# EEZ_PSU_power_board_r5B9.net
KiCad netlist of a schematic drawn in EAGLE
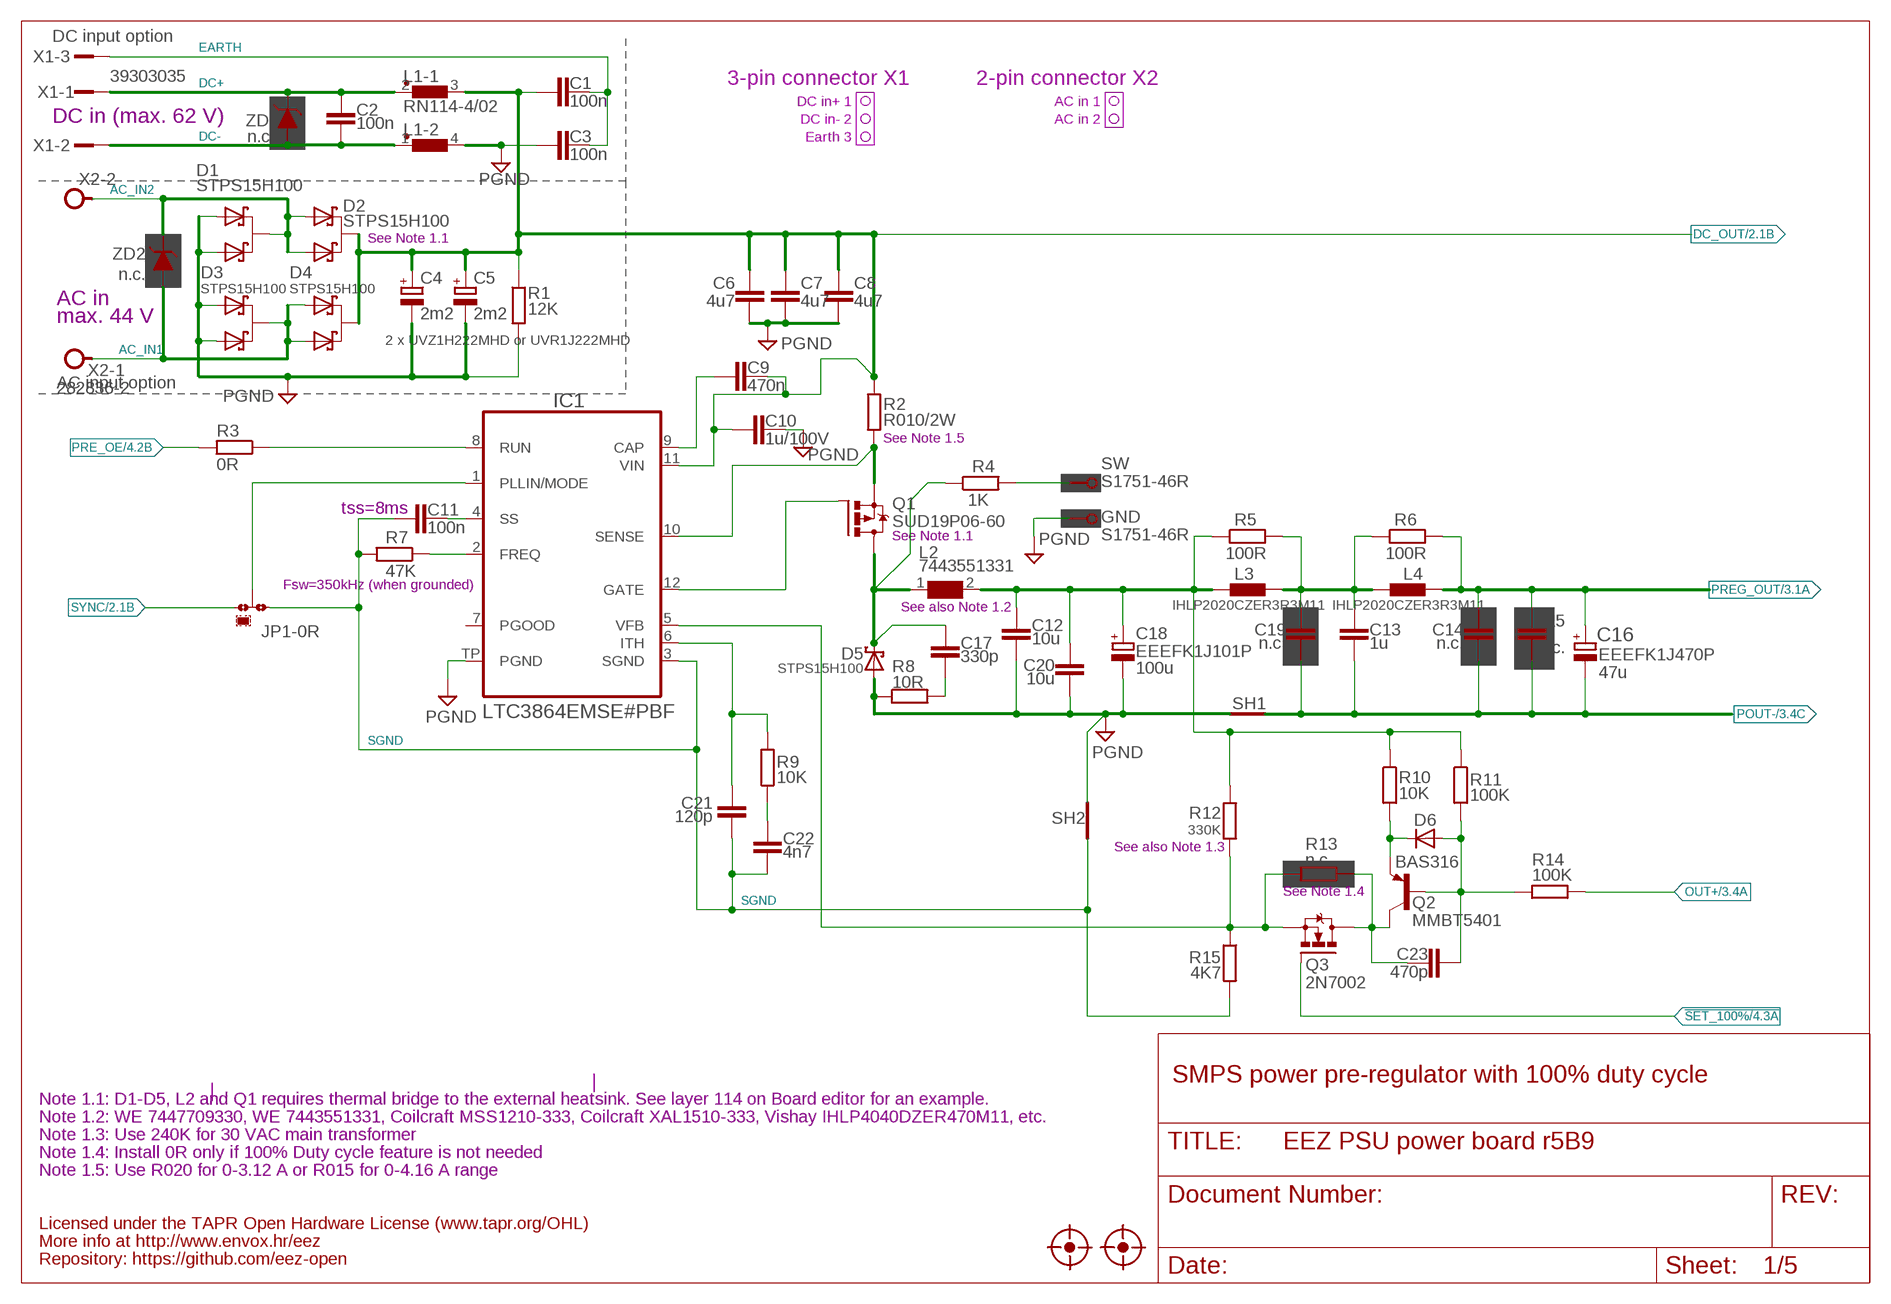
[diagram p0: schematic, sheet 1]
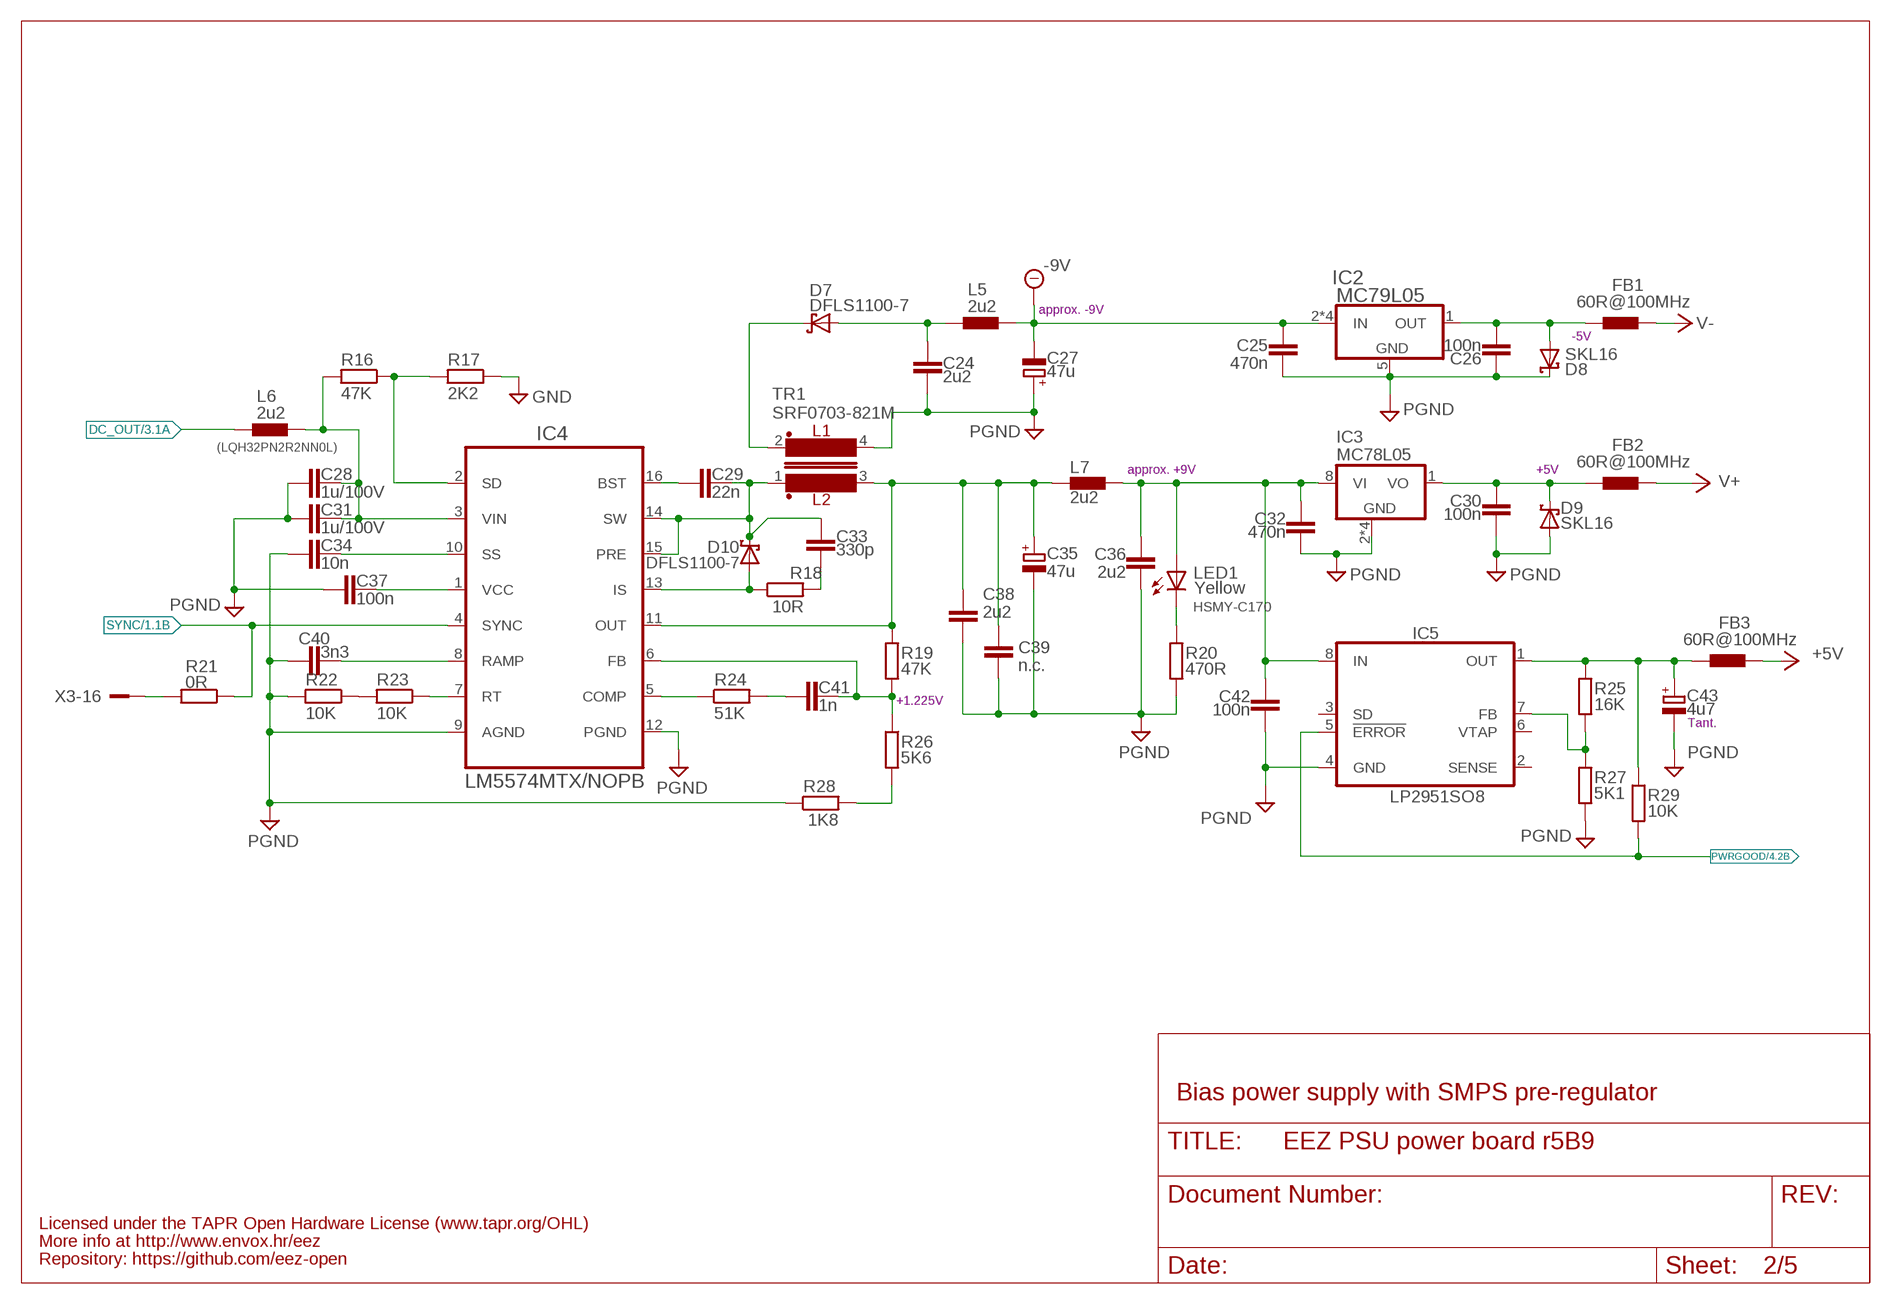
[diagram p1: schematic, sheet 2]
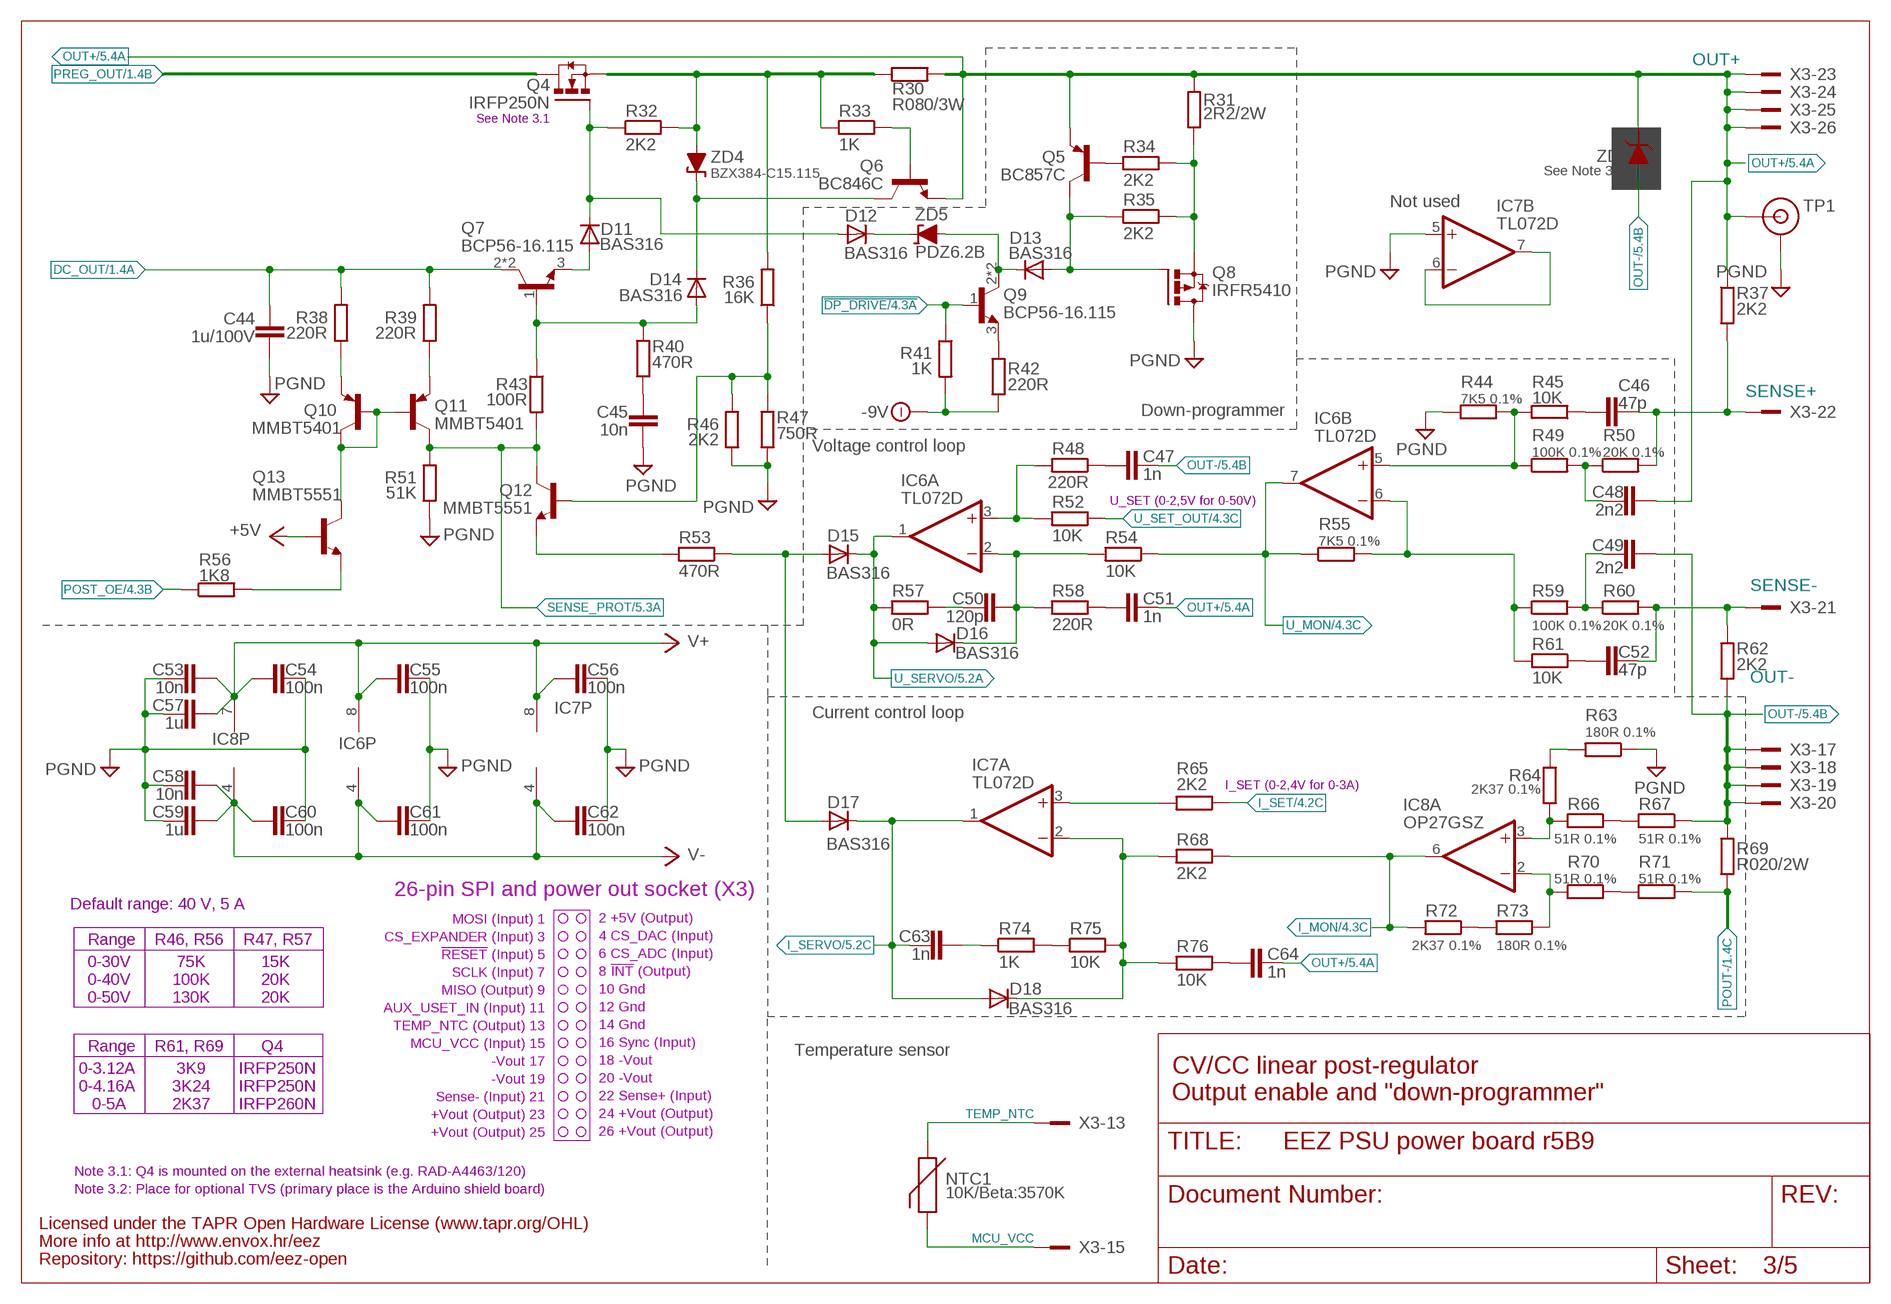
[diagram p2: schematic, sheet 3]
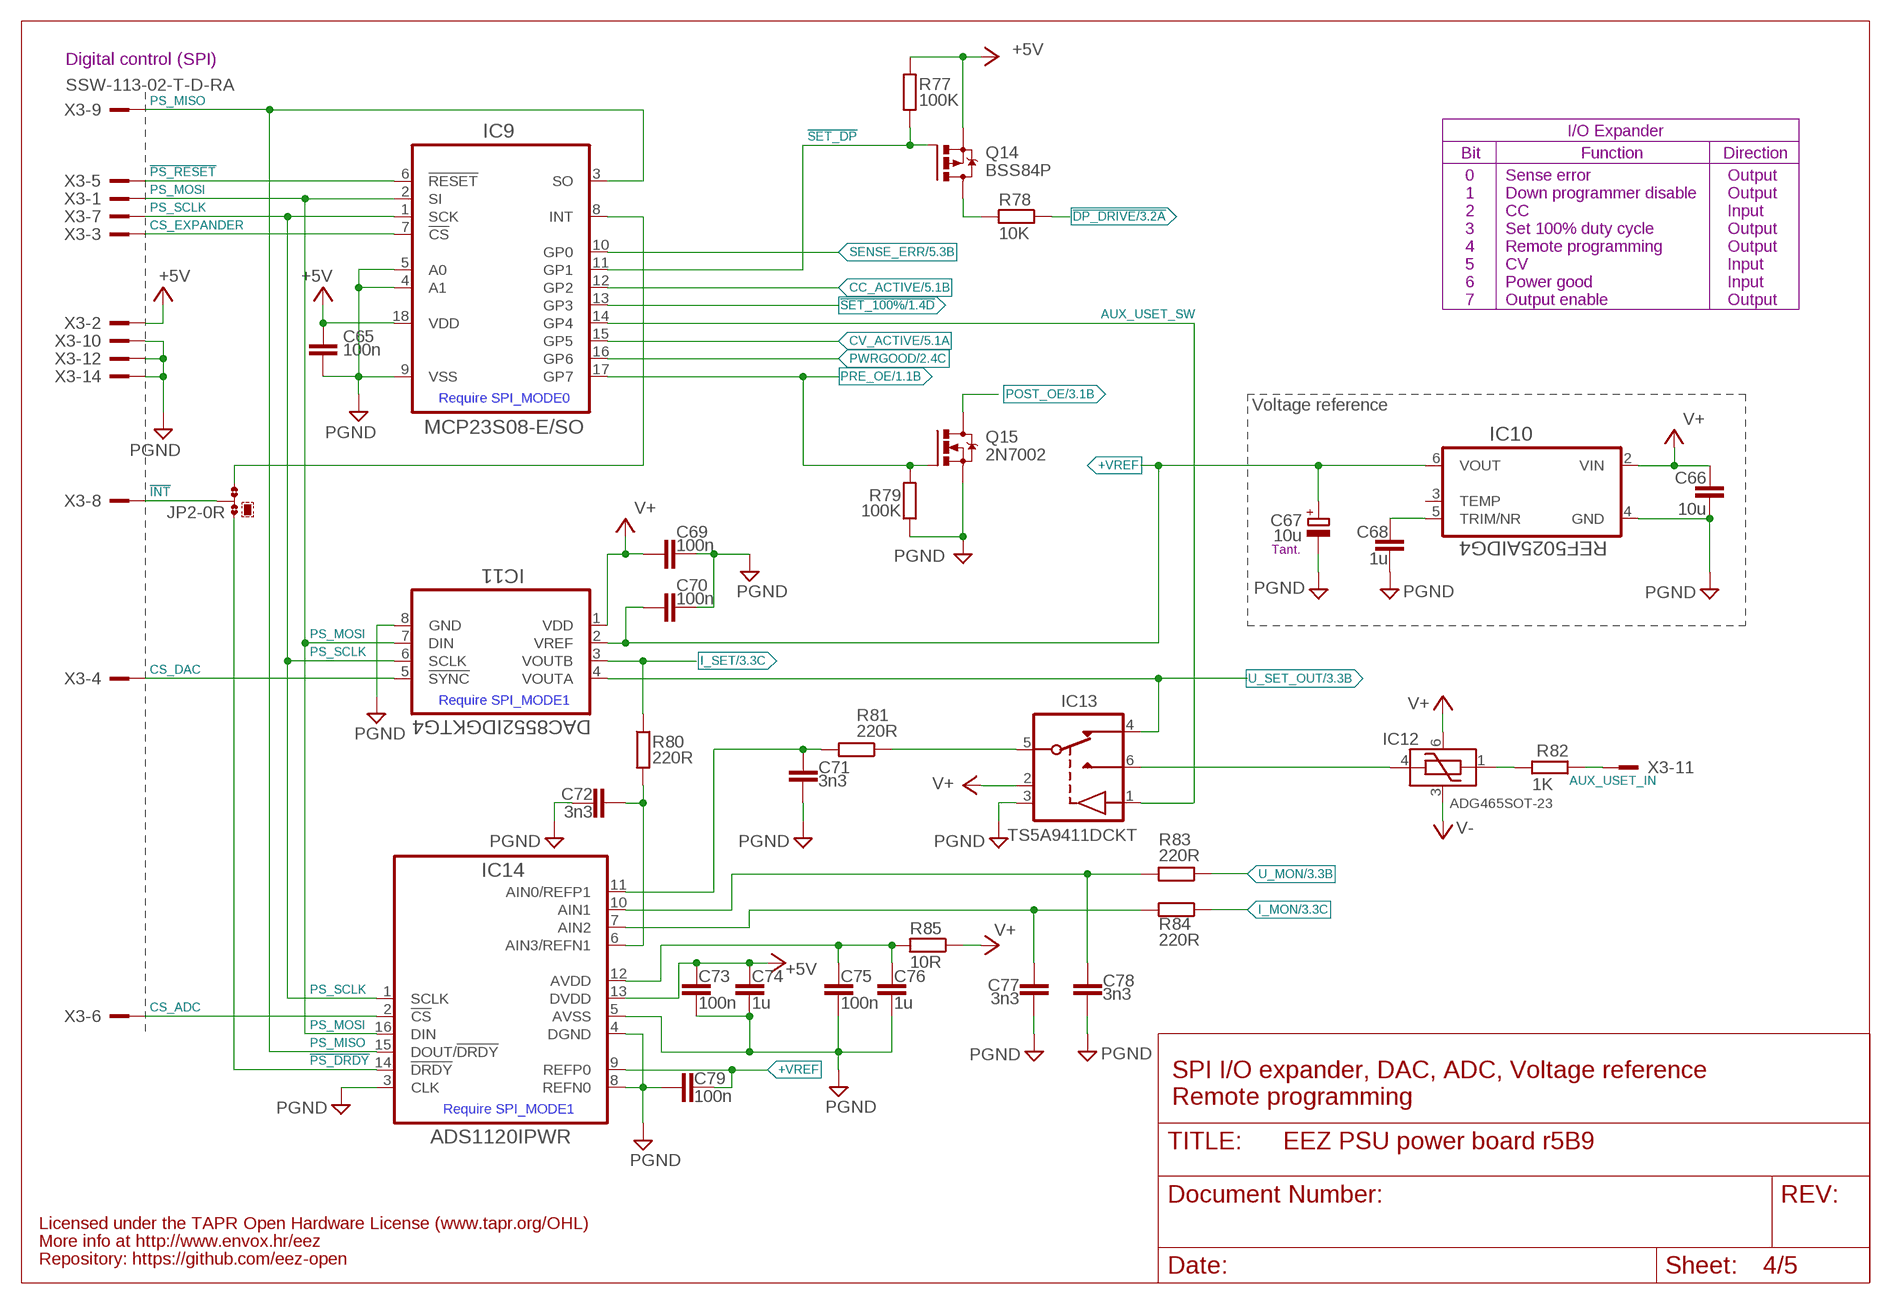
[diagram p3: schematic, sheet 4]
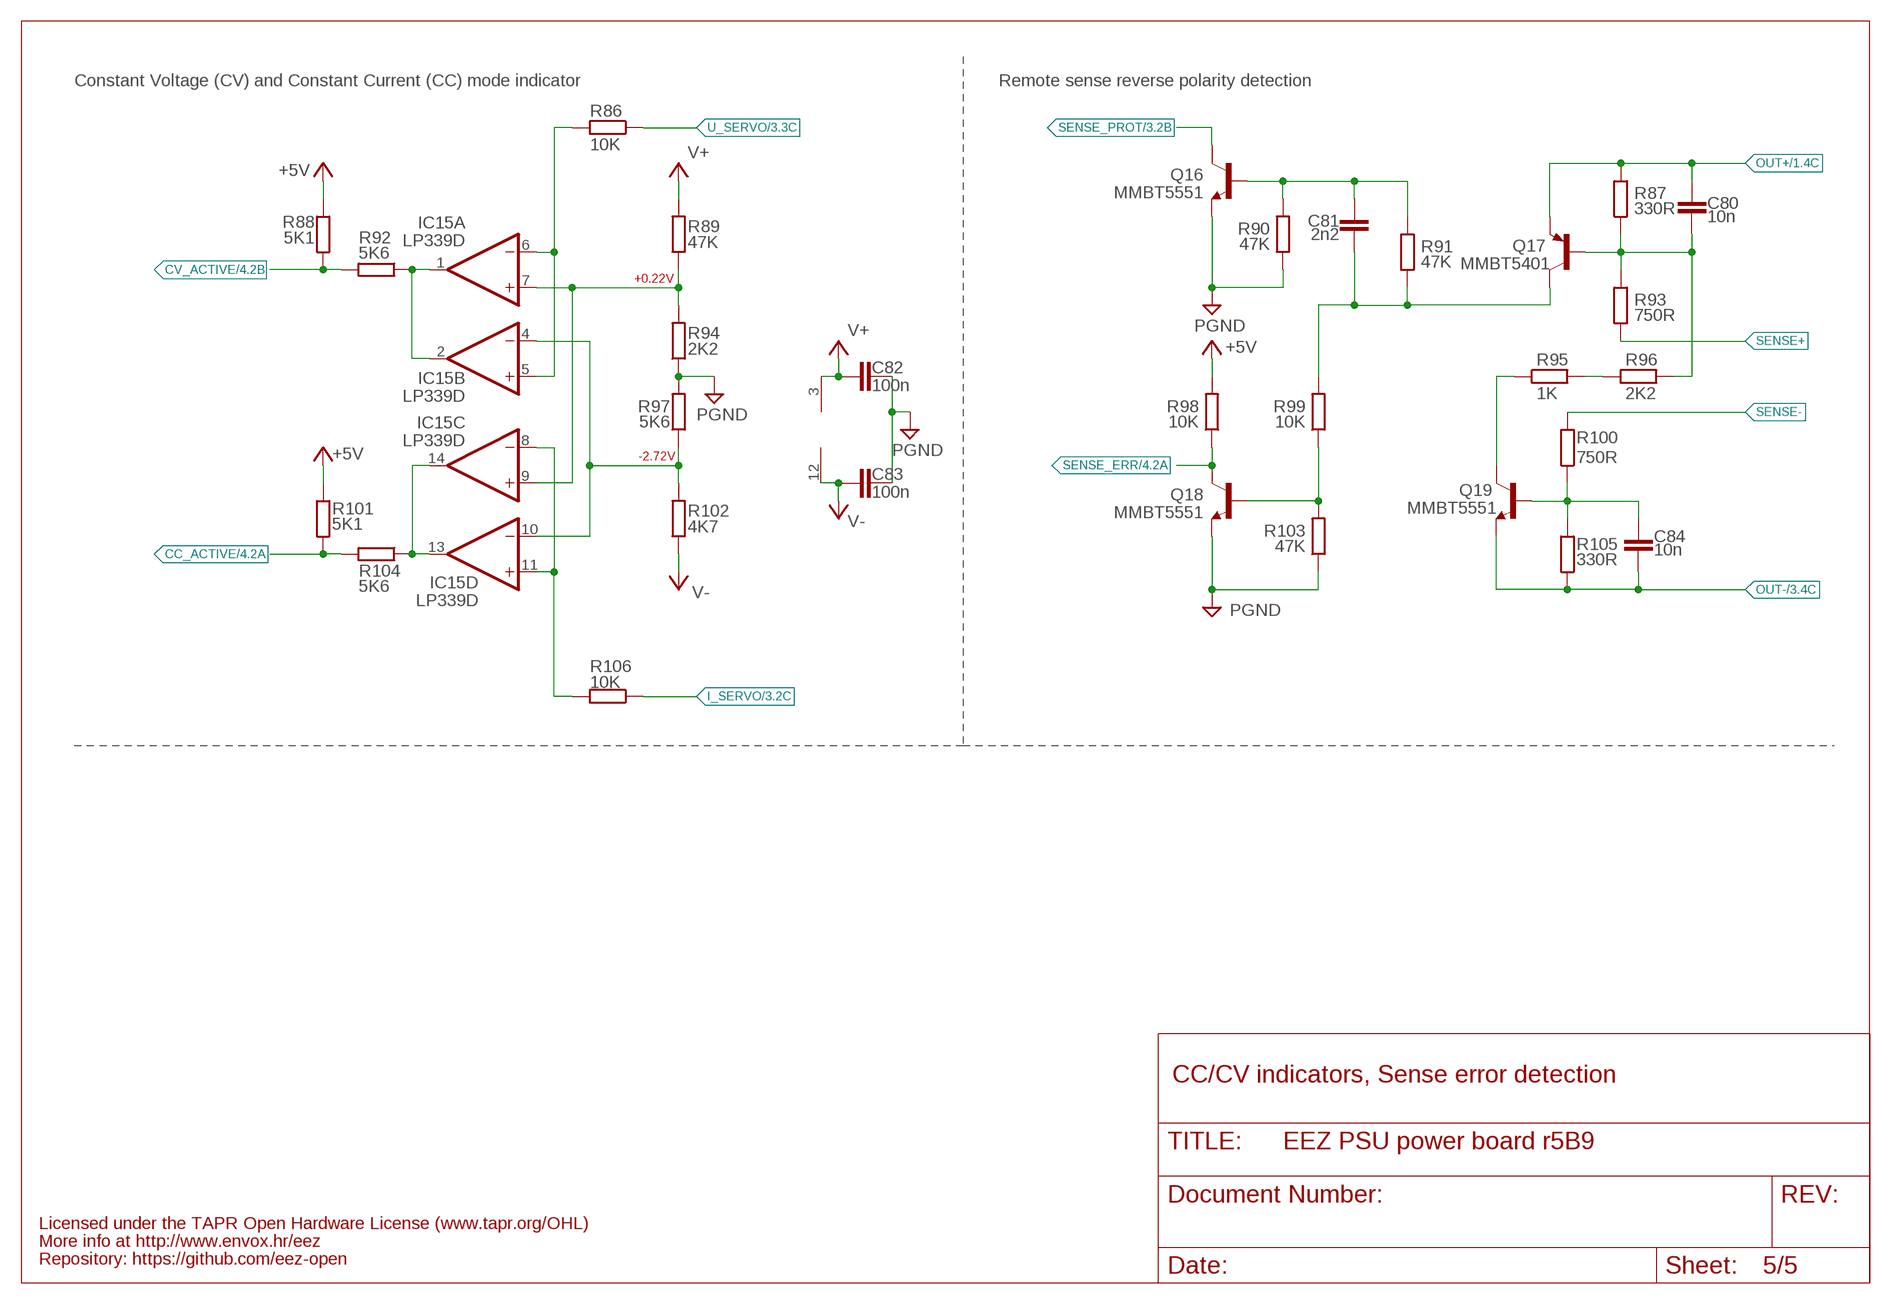
[diagram p4: schematic, sheet 5]

(export (version "E")
  (design (tool "Eeschema 10.0.6"))
  (components
    (comp (ref "C65")
      (value "100n")
      (footprint "eagle-import:C0603")
      (libsource (lib "eagle-import") (part "C-EUC0603"))
    )
    (comp (ref "C66")
      (value "10u")
      (footprint "eagle-import:C1210")
      (libsource (lib "eagle-import") (part "C-EUC1210"))
    )
    (comp (ref "C67")
      (value "10u")
      (footprint "eagle-import:EC1206")
      (libsource (lib "eagle-import") (part "ECAP1206"))
    )
    (comp (ref "C68")
      (value "1u")
      (footprint "eagle-import:C0805")
      (libsource (lib "eagle-import") (part "C-EUC0805"))
    )
    (comp (ref "C69")
      (value "100n")
      (footprint "eagle-import:C0603")
      (libsource (lib "eagle-import") (part "C-EUC0603"))
    )
    (comp (ref "C70")
      (value "100n")
      (footprint "eagle-import:C0603")
      (libsource (lib "eagle-import") (part "C-EUC0603"))
    )
    (comp (ref "C71")
      (value "3n3")
      (footprint "eagle-import:C0805")
      (libsource (lib "eagle-import") (part "C-EUC0805"))
    )
    (comp (ref "C72")
      (value "3n3")
      (footprint "eagle-import:C0805")
      (libsource (lib "eagle-import") (part "C-EUC0805"))
    )
    (comp (ref "C73")
      (value "100n")
      (footprint "eagle-import:C0603")
      (libsource (lib "eagle-import") (part "C-EUC0603"))
    )
    (comp (ref "C74")
      (value "1u")
      (footprint "eagle-import:C0805")
      (libsource (lib "eagle-import") (part "C-EUC0805"))
    )
    (comp (ref "C75")
      (value "100n")
      (footprint "eagle-import:C0603")
      (libsource (lib "eagle-import") (part "C-EUC0603"))
    )
    (comp (ref "C76")
      (value "1u")
      (footprint "eagle-import:C0805")
      (libsource (lib "eagle-import") (part "C-EUC0805"))
    )
    (comp (ref "C77")
      (value "3n3")
      (footprint "eagle-import:C0805")
      (libsource (lib "eagle-import") (part "C-EUC0805"))
    )
    (comp (ref "C78")
      (value "3n3")
      (footprint "eagle-import:C0805")
      (libsource (lib "eagle-import") (part "C-EUC0805"))
    )
    (comp (ref "C79")
      (value "100n")
      (footprint "eagle-import:C0603")
      (libsource (lib "eagle-import") (part "C-EUC0603"))
    )
    (comp (ref "IC9")
      (value "MCP23S08-E/SO")
      (footprint "eagle-import:SOIC127P1030X265-18N")
      (libsource (lib "eagle-import") (part "MCP23S08"))
    )
    (comp (ref "IC10")
      (value "REF5025AIDG4")
      (footprint "eagle-import:SOIC127P600X175-8N")
      (libsource (lib "eagle-import") (part "REF50XX"))
    )
    (comp (ref "IC11")
      (value "DAC8552IDGKTG4")
      (footprint "eagle-import:DGK8-M")
      (libsource (lib "eagle-import") (part "DAC8552_DGK_8M"))
    )
    (comp (ref "IC12")
      (value "ADG465SOT-23")
      (footprint "eagle-import:SOT95P280X145-6N")
      (libsource (lib "eagle-import") (part "ADG465SOT-23"))
    )
    (comp (ref "IC13")
      (value "TS5A9411DCKT")
      (footprint "eagle-import:SOT65P210X110-6N")
      (libsource (lib "eagle-import") (part "TS5A9411DCKT"))
    )
    (comp (ref "IC14")
      (value "ADS1120IPWR")
      (footprint "eagle-import:PW(R-PDSO-G16)")
      (libsource (lib "eagle-import") (part "ADS1120TSSOP-16"))
    )
    (comp (ref "JP2")
      (value "0R-JUMPA")
      (footprint "eagle-import:A0R-JMP")
      (libsource (lib "eagle-import") (part "0R-JUMPA"))
    )
    (comp (ref "Q14")
      (value "BSS84P")
      (footprint "eagle-import:SOT95P237X112-3N")
      (fields (field (name "MPN") "IRLML2246TRPBF"))
      (libsource (lib "eagle-import") (part "IRLML2246TRPBF"))
    )
    (comp (ref "Q15")
      (value "2N7002")
      (footprint "eagle-import:SOT103P240X110-3N")
      (fields
        (field (name "MPN") "2N7002-7-F")
        (field (name "MPN_1") "2N7002-7-F")
        (field (name "OC_FARNELL") "1713823")
        (field (name "OC_NEWARK") "25R5679")
        (field (name "PACKAGE") "SOT-23-3")
        (field (name "SUPPLIER") "DIODES INC.")
      )
      (libsource (lib "eagle-import") (part "2N7002"))
    )
    (comp (ref "R77")
      (value "100K")
      (footprint "eagle-import:R0805")
      (libsource (lib "eagle-import") (part "R-EU_R0805"))
    )
    (comp (ref "R78")
      (value "10K")
      (footprint "eagle-import:R0805")
      (libsource (lib "eagle-import") (part "R-EU_R0805"))
    )
    (comp (ref "R79")
      (value "100K")
      (footprint "eagle-import:R0805")
      (libsource (lib "eagle-import") (part "R-EU_R0805"))
    )
    (comp (ref "R80")
      (value "220R")
      (footprint "eagle-import:R0805")
      (libsource (lib "eagle-import") (part "R-EU_R0805"))
    )
    (comp (ref "R81")
      (value "220R")
      (footprint "eagle-import:R0805")
      (libsource (lib "eagle-import") (part "R-EU_R0805"))
    )
    (comp (ref "R82")
      (value "1K")
      (footprint "eagle-import:R0805")
      (libsource (lib "eagle-import") (part "R-EU_R0805"))
    )
    (comp (ref "R83")
      (value "220R")
      (footprint "eagle-import:R0805")
      (libsource (lib "eagle-import") (part "R-EU_R0805"))
    )
    (comp (ref "R84")
      (value "220R")
      (footprint "eagle-import:R0805")
      (libsource (lib "eagle-import") (part "R-EU_R0805"))
    )
    (comp (ref "R85")
      (value "10R")
      (footprint "eagle-import:R1206")
      (libsource (lib "eagle-import") (part "R-EU_R1206"))
    )
    (comp (ref "X3")
      (value "SSW-113-02-T-D-RA")
      (footprint "eagle-import:SSW-113-02-T-D-RA")
      (fields (field (name "FARNELL") "1805583"))
      (libsource (lib "eagle-import") (part "SSW-113-02-T-D-RA"))
    )
    (comp (ref "C24")
      (value "2u2")
      (footprint "eagle-import:C0805")
      (libsource (lib "eagle-import") (part "C-EUC0805"))
    )
    (comp (ref "C25")
      (value "470n")
      (footprint "eagle-import:C0805")
      (libsource (lib "eagle-import") (part "C-EUC0805"))
    )
    (comp (ref "C26")
      (value "100n")
      (footprint "eagle-import:C0603")
      (libsource (lib "eagle-import") (part "C-EUC0603"))
    )
    (comp (ref "C27")
      (value "47u")
      (footprint "eagle-import:CAPAE660X610N")
      (libsource (lib "eagle-import") (part "ECAPPANASONIC_H"))
    )
    (comp (ref "C28")
      (value "1u/100V")
      (footprint "eagle-import:C1206")
      (libsource (lib "eagle-import") (part "C-EUC1206"))
    )
    (comp (ref "C29")
      (value "22n")
      (footprint "eagle-import:C0805")
      (libsource (lib "eagle-import") (part "C-EUC0805"))
    )
    (comp (ref "C30")
      (value "100n")
      (footprint "eagle-import:C0603")
      (libsource (lib "eagle-import") (part "C-EUC0603"))
    )
    (comp (ref "C31")
      (value "1u/100V")
      (footprint "eagle-import:C1206")
      (libsource (lib "eagle-import") (part "C-EUC1206"))
    )
    (comp (ref "C32")
      (value "470n")
      (footprint "eagle-import:C0805")
      (libsource (lib "eagle-import") (part "C-EUC0805"))
    )
    (comp (ref "C33")
      (value "330p")
      (footprint "eagle-import:C0805")
      (libsource (lib "eagle-import") (part "C-EUC0805"))
    )
    (comp (ref "C34")
      (value "10n")
      (footprint "eagle-import:C0805")
      (libsource (lib "eagle-import") (part "C-EUC0805"))
    )
    (comp (ref "C35")
      (value "47u")
      (footprint "eagle-import:CAPAE660X610N")
      (libsource (lib "eagle-import") (part "ECAPPANASONIC_H"))
    )
    (comp (ref "C36")
      (value "2u2")
      (footprint "eagle-import:C0805")
      (libsource (lib "eagle-import") (part "C-EUC0805"))
    )
    (comp (ref "C37")
      (value "100n")
      (footprint "eagle-import:C0603")
      (libsource (lib "eagle-import") (part "C-EUC0603"))
    )
    (comp (ref "C38")
      (value "2u2")
      (footprint "eagle-import:C0805")
      (libsource (lib "eagle-import") (part "C-EUC0805"))
    )
    (comp (ref "C39")
      (value "n.c.")
      (footprint "eagle-import:C0805")
      (libsource (lib "eagle-import") (part "C-EUC0805"))
    )
    (comp (ref "C40")
      (value "3n3")
      (footprint "eagle-import:C0805")
      (libsource (lib "eagle-import") (part "C-EUC0805"))
    )
    (comp (ref "C41")
      (value "1n")
      (footprint "eagle-import:C0805")
      (libsource (lib "eagle-import") (part "C-EUC0805"))
    )
    (comp (ref "C42")
      (value "100n")
      (footprint "eagle-import:C0603")
      (libsource (lib "eagle-import") (part "C-EUC0603"))
    )
    (comp (ref "C43")
      (value "4u7")
      (footprint "eagle-import:EC1206")
      (libsource (lib "eagle-import") (part "ECAP1206"))
    )
    (comp (ref "D7")
      (value "DFLS1100-7")
      (footprint "eagle-import:SOD123")
      (libsource (lib "eagle-import") (part "SCHOTTKYSOD123"))
    )
    (comp (ref "D8")
      (value "SKL16")
      (footprint "eagle-import:SOD123")
      (libsource (lib "eagle-import") (part "SCHOTTKYSOD123"))
    )
    (comp (ref "D9")
      (value "SKL16")
      (footprint "eagle-import:SOD123")
      (libsource (lib "eagle-import") (part "SCHOTTKYSOD123"))
    )
    (comp (ref "D10")
      (value "DFLS1100-7")
      (footprint "eagle-import:SOD123")
      (libsource (lib "eagle-import") (part "SCHOTTKYSOD123"))
    )
    (comp (ref "FB1")
      (value "60R@100MHz")
      (footprint "eagle-import:BEAD0603")
      (libsource (lib "eagle-import") (part "FERRITE_BEAD0603"))
    )
    (comp (ref "FB2")
      (value "60R@100MHz")
      (footprint "eagle-import:BEAD0603")
      (libsource (lib "eagle-import") (part "FERRITE_BEAD0603"))
    )
    (comp (ref "FB3")
      (value "60R@100MHz")
      (footprint "eagle-import:BEAD0603")
      (libsource (lib "eagle-import") (part "FERRITE_BEAD0603"))
    )
    (comp (ref "IC2")
      (value "MC79L05")
      (footprint "eagle-import:SOIC127P600X173-8N")
      (libsource (lib "eagle-import") (part "MC79LXXSOIC"))
    )
    (comp (ref "IC3")
      (value "MC78L05")
      (footprint "eagle-import:SOIC127P600X173-8N")
      (libsource (lib "eagle-import") (part "MC78LXXSOIC8"))
    )
    (comp (ref "IC4")
      (value "LM5574MTX/NOPB")
      (footprint "eagle-import:SOP65P640X110-16N")
      (fields (field (name "MPN") "LM5574MT"))
      (libsource (lib "eagle-import") (part "LM5574"))
    )
    (comp (ref "IC5")
      (value "LP2951SO8")
      (footprint "eagle-import:SOIC127P600X175-8N")
      (libsource (lib "eagle-import") (part "LP2951SO8"))
    )
    (comp (ref "L5")
      (value "2u2")
      (footprint "eagle-import:L1210")
      (libsource (lib "eagle-import") (part "L1210"))
    )
    (comp (ref "L6")
      (value "2u2")
      (footprint "eagle-import:L1210")
      (libsource (lib "eagle-import") (part "L1210"))
    )
    (comp (ref "L7")
      (value "2u2")
      (footprint "eagle-import:L1210")
      (libsource (lib "eagle-import") (part "L1210"))
    )
    (comp (ref "LED1")
      (value "HSMY-C170")
      (footprint "eagle-import:LED_0805")
      (libsource (lib "eagle-import") (part "LED0805"))
    )
    (comp (ref "R16")
      (value "47K")
      (footprint "eagle-import:R0805")
      (libsource (lib "eagle-import") (part "R-EU_R0805"))
    )
    (comp (ref "R17")
      (value "2K2")
      (footprint "eagle-import:R0805")
      (libsource (lib "eagle-import") (part "R-EU_R0805"))
    )
    (comp (ref "R18")
      (value "10R")
      (footprint "eagle-import:R1206")
      (libsource (lib "eagle-import") (part "R-EU_R1206"))
    )
    (comp (ref "R19")
      (value "47K")
      (footprint "eagle-import:R0805")
      (libsource (lib "eagle-import") (part "R-EU_R0805"))
    )
    (comp (ref "R20")
      (value "470R")
      (footprint "eagle-import:R0805")
      (libsource (lib "eagle-import") (part "R-EU_R0805"))
    )
    (comp (ref "R21")
      (value "0R")
      (footprint "eagle-import:R0805")
      (libsource (lib "eagle-import") (part "R-EU_R0805"))
    )
    (comp (ref "R22")
      (value "10K")
      (footprint "eagle-import:R0805")
      (libsource (lib "eagle-import") (part "R-EU_R0805"))
    )
    (comp (ref "R23")
      (value "10K")
      (footprint "eagle-import:R0805")
      (libsource (lib "eagle-import") (part "R-EU_R0805"))
    )
    (comp (ref "R24")
      (value "51K")
      (footprint "eagle-import:R0805")
      (libsource (lib "eagle-import") (part "R-EU_R0805"))
    )
    (comp (ref "R25")
      (value "16K")
      (footprint "eagle-import:R0805")
      (libsource (lib "eagle-import") (part "R-EU_R0805"))
    )
    (comp (ref "R26")
      (value "5K6")
      (footprint "eagle-import:R0805")
      (libsource (lib "eagle-import") (part "R-EU_R0805"))
    )
    (comp (ref "R27")
      (value "5K1")
      (footprint "eagle-import:R0805")
      (libsource (lib "eagle-import") (part "R-EU_R0805"))
    )
    (comp (ref "R28")
      (value "1K8")
      (footprint "eagle-import:R0805")
      (libsource (lib "eagle-import") (part "R-EU_R0805"))
    )
    (comp (ref "R29")
      (value "10K")
      (footprint "eagle-import:R0805")
      (libsource (lib "eagle-import") (part "R-EU_R0805"))
    )
    (comp (ref "TR1")
      (value "SRF0703-821M")
      (footprint "eagle-import:SRF0703")
      (libsource (lib "eagle-import") (part "BOURNS_SRF0703INV"))
    )
    (comp (ref "C1")
      (value "100n")
      (footprint "eagle-import:C1206")
      (libsource (lib "eagle-import") (part "C-EUC1206"))
    )
    (comp (ref "C2")
      (value "100n")
      (footprint "eagle-import:C1206")
      (libsource (lib "eagle-import") (part "C-EUC1206"))
    )
    (comp (ref "C3")
      (value "100n")
      (footprint "eagle-import:C1206")
      (libsource (lib "eagle-import") (part "C-EUC1206"))
    )
    (comp (ref "C4")
      (value "2m2")
      (footprint "eagle-import:ECAP7.5_18")
      (libsource (lib "eagle-import") (part "ECAP7.5G_18MM"))
    )
    (comp (ref "C5")
      (value "2m2")
      (footprint "eagle-import:ECAP7.5_18")
      (libsource (lib "eagle-import") (part "ECAP7.5G_18MM"))
    )
    (comp (ref "C6")
      (value "4u7")
      (footprint "eagle-import:C1210")
      (libsource (lib "eagle-import") (part "C-EUC1210"))
    )
    (comp (ref "C7")
      (value "4u7")
      (footprint "eagle-import:C1210")
      (libsource (lib "eagle-import") (part "C-EUC1210"))
    )
    (comp (ref "C8")
      (value "4u7")
      (footprint "eagle-import:C1210")
      (libsource (lib "eagle-import") (part "C-EUC1210"))
    )
    (comp (ref "C9")
      (value "470n")
      (footprint "eagle-import:C0805")
      (libsource (lib "eagle-import") (part "C-EUC0805"))
    )
    (comp (ref "C10")
      (value "1u/100V")
      (footprint "eagle-import:C1206")
      (libsource (lib "eagle-import") (part "C-EUC1206"))
    )
    (comp (ref "C11")
      (value "100n")
      (footprint "eagle-import:C0603")
      (libsource (lib "eagle-import") (part "C-EUC0603"))
    )
    (comp (ref "C12")
      (value "10u")
      (footprint "eagle-import:C1210")
      (libsource (lib "eagle-import") (part "C-EUC1210"))
    )
    (comp (ref "C13")
      (value "1u")
      (footprint "eagle-import:C0805")
      (libsource (lib "eagle-import") (part "C-EUC0805"))
    )
    (comp (ref "C14")
      (value "n.c.")
      (footprint "eagle-import:C0805")
      (libsource (lib "eagle-import") (part "C-EUC0805"))
    )
    (comp (ref "C15")
      (value "n.c.")
      (footprint "eagle-import:C0805")
      (libsource (lib "eagle-import") (part "C-EUC0805"))
    )
    (comp (ref "C16")
      (value "EEEFK1J470P")
      (footprint "eagle-import:CAPAE830X1050N")
      (fields (field (name "MPN") "EEE-FK1J470P") (field (name "TOLERANCE") "±20 %"))
      (libsource (lib "eagle-import") (part "EEE--CASE-FFK1J470P"))
    )
    (comp (ref "C17")
      (value "330p")
      (footprint "eagle-import:C0805")
      (libsource (lib "eagle-import") (part "C-EUC0805"))
    )
    (comp (ref "C18")
      (value "EEEFK1J101P")
      (footprint "eagle-import:PANASONIC_F")
      (libsource (lib "eagle-import") (part "ECAPF"))
    )
    (comp (ref "C19")
      (value "n.c.")
      (footprint "eagle-import:C0805")
      (libsource (lib "eagle-import") (part "C-EUC0805"))
    )
    (comp (ref "C20")
      (value "10u")
      (footprint "eagle-import:C1210")
      (libsource (lib "eagle-import") (part "C-EUC1210"))
    )
    (comp (ref "C21")
      (value "120p")
      (footprint "eagle-import:C0805")
      (libsource (lib "eagle-import") (part "C-EUC0805"))
    )
    (comp (ref "C22")
      (value "4n7")
      (footprint "eagle-import:C0805")
      (libsource (lib "eagle-import") (part "C-EUC0805"))
    )
    (comp (ref "C23")
      (value "470p")
      (footprint "eagle-import:C0805")
      (libsource (lib "eagle-import") (part "C-EUC0805"))
    )
    (comp (ref "D1")
      (value "STPS15H100")
      (footprint "eagle-import:TO252@1")
      (libsource (lib "eagle-import") (part "VS-6CWQ06FNPBF"))
    )
    (comp (ref "D2")
      (value "STPS15H100")
      (footprint "eagle-import:TO252@1")
      (libsource (lib "eagle-import") (part "VS-6CWQ06FNPBF"))
    )
    (comp (ref "D3")
      (value "STPS15H100")
      (footprint "eagle-import:TO252@1")
      (libsource (lib "eagle-import") (part "VS-6CWQ06FNPBF"))
    )
    (comp (ref "D4")
      (value "STPS15H100")
      (footprint "eagle-import:TO252@1")
      (libsource (lib "eagle-import") (part "VS-6CWQ06FNPBF"))
    )
    (comp (ref "D5")
      (value "STPS15H100")
      (footprint "eagle-import:TO252")
      (libsource (lib "eagle-import") (part "SCHOTTKYTO252"))
    )
    (comp (ref "D6")
      (value "BAS316")
      (footprint "eagle-import:SOD323-W")
      (libsource (lib "eagle-import") (part "DIODE-SOD323-W"))
    )
    (comp (ref "FM1")
      (value "FIDUCIAL_2")
      (footprint "eagle-import:FIDUCIAL_DUAL")
      (libsource (lib "eagle-import") (part "FIDUCIAL_2"))
    )
    (comp (ref "FM2")
      (value "FIDUCIAL_2")
      (footprint "eagle-import:FIDUCIAL_DUAL")
      (libsource (lib "eagle-import") (part "FIDUCIAL_2"))
    )
    (comp (ref "GND")
      (value "S1751-46R")
      (footprint "eagle-import:S1751-46R")
      (libsource (lib "eagle-import") (part "PCB_TEST_TABSMD"))
    )
    (comp (ref "IC1")
      (value "LTC3864EMSE#PBF")
      (footprint "eagle-import:LTC_05-08-1666")
      (libsource (lib "eagle-import") (part "LTC3864"))
    )
    (comp (ref "JP1")
      (value "0R-JUMPA")
      (footprint "eagle-import:A0R-JMP")
      (libsource (lib "eagle-import") (part "0R-JUMPA"))
    )
    (comp (ref "L1")
      (value "RN114-4/02")
      (footprint "eagle-import:RN114")
      (libsource (lib "eagle-import") (part "RN114"))
    )
    (comp (ref "L2")
      (value "7443551331")
      (footprint "eagle-import:WE-HCI_1350_1365")
      (libsource (lib "eagle-import") (part "WE-HCI_1350/1365-7443551331"))
    )
    (comp (ref "L3")
      (value "IHLP2020CZER3R3M11")
      (footprint "eagle-import:IHLP-2020BZ-11")
      (libsource (lib "eagle-import") (part "IHLP-2020BZ-11"))
    )
    (comp (ref "L4")
      (value "IHLP2020CZER3R3M11")
      (footprint "eagle-import:IHLP-2020BZ-11")
      (libsource (lib "eagle-import") (part "IHLP-2020BZ-11"))
    )
    (comp (ref "Q1")
      (value "SUD19P06-60")
      (footprint "eagle-import:TO229P990X239-3N")
      (libsource (lib "eagle-import") (part "P-MOSFETDPAK"))
    )
    (comp (ref "Q2")
      (value "MMBT5401")
      (footprint "eagle-import:SOT23-BEC")
      (libsource (lib "eagle-import") (part "-PNP-SOT23-BECBC857B"))
    )
    (comp (ref "Q3")
      (value "2N7002")
      (footprint "eagle-import:SOT103P240X110-3N")
      (fields (field (name "MPN") "2N7002-7-F"))
      (libsource (lib "eagle-import") (part "2N7002"))
    )
    (comp (ref "R1")
      (value "12K")
      (footprint "eagle-import:R1206")
      (libsource (lib "eagle-import") (part "R-EU_R1206"))
    )
    (comp (ref "R2")
      (value "R010/2W")
      (footprint "eagle-import:R2512")
      (libsource (lib "eagle-import") (part "R-EU_R2512"))
    )
    (comp (ref "R3")
      (value "0R")
      (footprint "eagle-import:R0805")
      (libsource (lib "eagle-import") (part "R-EU_R0805"))
    )
    (comp (ref "R4")
      (value "1K")
      (footprint "eagle-import:R0805")
      (libsource (lib "eagle-import") (part "R-EU_R0805"))
    )
    (comp (ref "R5")
      (value "100R")
      (footprint "eagle-import:R0805")
      (libsource (lib "eagle-import") (part "R-EU_R0805"))
    )
    (comp (ref "R6")
      (value "100R")
      (footprint "eagle-import:R0805")
      (libsource (lib "eagle-import") (part "R-EU_R0805"))
    )
    (comp (ref "R7")
      (value "47K")
      (footprint "eagle-import:R0805")
      (libsource (lib "eagle-import") (part "R-EU_R0805"))
    )
    (comp (ref "R8")
      (value "10R")
      (footprint "eagle-import:R1206")
      (libsource (lib "eagle-import") (part "R-EU_R1206"))
    )
    (comp (ref "R9")
      (value "10K")
      (footprint "eagle-import:R0805")
      (libsource (lib "eagle-import") (part "R-EU_R0805"))
    )
    (comp (ref "R10")
      (value "10K")
      (footprint "eagle-import:R0805")
      (libsource (lib "eagle-import") (part "R-EU_R0805"))
    )
    (comp (ref "R11")
      (value "100K")
      (footprint "eagle-import:R0805")
      (libsource (lib "eagle-import") (part "R-EU_R0805"))
    )
    (comp (ref "R12")
      (value "330K")
      (footprint "eagle-import:R0805")
      (libsource (lib "eagle-import") (part "R-EU_R0805"))
    )
    (comp (ref "R13")
      (value "n.c.")
      (footprint "eagle-import:R0805")
      (libsource (lib "eagle-import") (part "R-EU_R0805"))
    )
    (comp (ref "R14")
      (value "100K")
      (footprint "eagle-import:R0805")
      (libsource (lib "eagle-import") (part "R-EU_R0805"))
    )
    (comp (ref "R15")
      (value "4K7")
      (footprint "eagle-import:R0805")
      (libsource (lib "eagle-import") (part "R-EU_R0805"))
    )
    (comp (ref "SH1")
      (value "Pgnd to Pout- short")
      (footprint "eagle-import:SHORT_NOHOLE")
      (libsource (lib "eagle-import") (part "SHORTNOHOLE"))
    )
    (comp (ref "SH2")
      (value "Sgnd to Pgnd short")
      (footprint "eagle-import:SHORT_NOHOLE")
      (libsource (lib "eagle-import") (part "SHORTNOHOLE"))
    )
    (comp (ref "SW")
      (value "S1751-46R")
      (footprint "eagle-import:S1751-46R")
      (libsource (lib "eagle-import") (part "PCB_TEST_TABSMD"))
    )
    (comp (ref "X1")
      (value "39303035")
      (footprint "eagle-import:MINIFIT_6659-3")
      (libsource (lib "eagle-import") (part "MINIFIT-3PIN"))
    )
    (comp (ref "X2")
      (value "282836-2")
      (footprint "eagle-import:TBLOCK5.0_2")
      (libsource (lib "eagle-import") (part "TBLOCK5.0_2A"))
    )
    (comp (ref "ZD1")
      (value "n.c.")
      (footprint "eagle-import:DO214AA")
      (libsource (lib "eagle-import") (part "P6SMB68A"))
    )
    (comp (ref "ZD2")
      (value "n.c.")
      (footprint "eagle-import:DO214AA")
      (libsource (lib "eagle-import") (part "P6SMB68A"))
    )
    (comp (ref "C80")
      (value "10n")
      (footprint "eagle-import:C0805")
      (libsource (lib "eagle-import") (part "C-EUC0805"))
    )
    (comp (ref "C81")
      (value "2n2")
      (footprint "eagle-import:C0805")
      (libsource (lib "eagle-import") (part "C-EUC0805"))
    )
    (comp (ref "C82")
      (value "100n")
      (footprint "eagle-import:C0603")
      (libsource (lib "eagle-import") (part "C-EUC0603"))
    )
    (comp (ref "C83")
      (value "100n")
      (footprint "eagle-import:C0603")
      (libsource (lib "eagle-import") (part "C-EUC0603"))
    )
    (comp (ref "C84")
      (value "10n")
      (footprint "eagle-import:C0805")
      (libsource (lib "eagle-import") (part "C-EUC0805"))
    )
    (comp (ref "IC15")
      (value "LP339D")
      (footprint "eagle-import:SOIC127P600X175-14N")
      (libsource (lib "eagle-import") (part "LM339SO14"))
    )
    (comp (ref "Q16")
      (value "MMBT5551")
      (footprint "eagle-import:SOT23-BEC")
      (libsource (lib "eagle-import") (part "-NPN-SOT23-BECMMBT5551LT1"))
    )
    (comp (ref "Q17")
      (value "MMBT5401")
      (footprint "eagle-import:SOT23-BEC")
      (libsource (lib "eagle-import") (part "-PNP-SOT23-BECBC857B"))
    )
    (comp (ref "Q18")
      (value "MMBT5551")
      (footprint "eagle-import:SOT23-BEC")
      (libsource (lib "eagle-import") (part "-NPN-SOT23-BECMMBT5551LT1"))
    )
    (comp (ref "Q19")
      (value "MMBT5551")
      (footprint "eagle-import:SOT23-BEC")
      (libsource (lib "eagle-import") (part "-NPN-SOT23-BECMMBT5551LT1"))
    )
    (comp (ref "R86")
      (value "10K")
      (footprint "eagle-import:R0805")
      (libsource (lib "eagle-import") (part "R-EU_R0805"))
    )
    (comp (ref "R87")
      (value "330R")
      (footprint "eagle-import:R0805")
      (libsource (lib "eagle-import") (part "R-EU_R0805"))
    )
    (comp (ref "R88")
      (value "5K1")
      (footprint "eagle-import:R0805")
      (libsource (lib "eagle-import") (part "R-EU_R0805"))
    )
    (comp (ref "R89")
      (value "47K")
      (footprint "eagle-import:R0805")
      (libsource (lib "eagle-import") (part "R-EU_R0805"))
    )
    (comp (ref "R90")
      (value "47K")
      (footprint "eagle-import:R0805")
      (libsource (lib "eagle-import") (part "R-EU_R0805"))
    )
    (comp (ref "R91")
      (value "47K")
      (footprint "eagle-import:R0805")
      (libsource (lib "eagle-import") (part "R-EU_R0805"))
    )
    (comp (ref "R92")
      (value "5K6")
      (footprint "eagle-import:R0805")
      (libsource (lib "eagle-import") (part "R-EU_R0805"))
    )
    (comp (ref "R93")
      (value "750R")
      (footprint "eagle-import:R0805")
      (libsource (lib "eagle-import") (part "R-EU_R0805"))
    )
    (comp (ref "R94")
      (value "2K2")
      (footprint "eagle-import:R0805")
      (libsource (lib "eagle-import") (part "R-EU_R0805"))
    )
    (comp (ref "R95")
      (value "1K")
      (footprint "eagle-import:R0805")
      (libsource (lib "eagle-import") (part "R-EU_R0805"))
    )
    (comp (ref "R96")
      (value "2K2")
      (footprint "eagle-import:R0805")
      (libsource (lib "eagle-import") (part "R-EU_R0805"))
    )
    (comp (ref "R97")
      (value "5K6")
      (footprint "eagle-import:R0805")
      (libsource (lib "eagle-import") (part "R-EU_R0805"))
    )
    (comp (ref "R98")
      (value "10K")
      (footprint "eagle-import:R0805")
      (libsource (lib "eagle-import") (part "R-EU_R0805"))
    )
    (comp (ref "R99")
      (value "10K")
      (footprint "eagle-import:R0805")
      (libsource (lib "eagle-import") (part "R-EU_R0805"))
    )
    (comp (ref "R100")
      (value "750R")
      (footprint "eagle-import:R0805")
      (libsource (lib "eagle-import") (part "R-EU_R0805"))
    )
    (comp (ref "R101")
      (value "5K1")
      (footprint "eagle-import:R0805")
      (libsource (lib "eagle-import") (part "R-EU_R0805"))
    )
    (comp (ref "R102")
      (value "4K7")
      (footprint "eagle-import:R0805")
      (libsource (lib "eagle-import") (part "R-EU_R0805"))
    )
    (comp (ref "R103")
      (value "47K")
      (footprint "eagle-import:R0805")
      (libsource (lib "eagle-import") (part "R-EU_R0805"))
    )
    (comp (ref "R104")
      (value "5K6")
      (footprint "eagle-import:R0805")
      (libsource (lib "eagle-import") (part "R-EU_R0805"))
    )
    (comp (ref "R105")
      (value "330R")
      (footprint "eagle-import:R0805")
      (libsource (lib "eagle-import") (part "R-EU_R0805"))
    )
    (comp (ref "R106")
      (value "10K")
      (footprint "eagle-import:R0805")
      (libsource (lib "eagle-import") (part "R-EU_R0805"))
    )
    (comp (ref "C44")
      (value "1u/100V")
      (footprint "eagle-import:C1206")
      (libsource (lib "eagle-import") (part "C-EUC1206"))
    )
    (comp (ref "C45")
      (value "10n")
      (footprint "eagle-import:C0805")
      (libsource (lib "eagle-import") (part "C-EUC0805"))
    )
    (comp (ref "C46")
      (value "47p")
      (footprint "eagle-import:C0805")
      (libsource (lib "eagle-import") (part "C-EUC0805"))
    )
    (comp (ref "C47")
      (value "1n")
      (footprint "eagle-import:C0805")
      (libsource (lib "eagle-import") (part "C-EUC0805"))
    )
    (comp (ref "C48")
      (value "2n2")
      (footprint "eagle-import:C0805")
      (libsource (lib "eagle-import") (part "C-EUC0805"))
    )
    (comp (ref "C49")
      (value "2n2")
      (footprint "eagle-import:C0805")
      (libsource (lib "eagle-import") (part "C-EUC0805"))
    )
    (comp (ref "C50")
      (value "120p")
      (footprint "eagle-import:C0805")
      (libsource (lib "eagle-import") (part "C-EUC0805"))
    )
    (comp (ref "C51")
      (value "1n")
      (footprint "eagle-import:C0805")
      (libsource (lib "eagle-import") (part "C-EUC0805"))
    )
    (comp (ref "C52")
      (value "47p")
      (footprint "eagle-import:C0805")
      (libsource (lib "eagle-import") (part "C-EUC0805"))
    )
    (comp (ref "C53")
      (value "10n")
      (footprint "eagle-import:C0805")
      (libsource (lib "eagle-import") (part "C-EUC0805"))
    )
    (comp (ref "C54")
      (value "100n")
      (footprint "eagle-import:C0603")
      (libsource (lib "eagle-import") (part "C-EUC0603"))
    )
    (comp (ref "C55")
      (value "100n")
      (footprint "eagle-import:C0603")
      (libsource (lib "eagle-import") (part "C-EUC0603"))
    )
    (comp (ref "C56")
      (value "100n")
      (footprint "eagle-import:C0603")
      (libsource (lib "eagle-import") (part "C-EUC0603"))
    )
    (comp (ref "C57")
      (value "1u")
      (footprint "eagle-import:C0805")
      (libsource (lib "eagle-import") (part "C-EUC0805"))
    )
    (comp (ref "C58")
      (value "10n")
      (footprint "eagle-import:C0805")
      (libsource (lib "eagle-import") (part "C-EUC0805"))
    )
    (comp (ref "C59")
      (value "1u")
      (footprint "eagle-import:C0805")
      (libsource (lib "eagle-import") (part "C-EUC0805"))
    )
    (comp (ref "C60")
      (value "100n")
      (footprint "eagle-import:C0603")
      (libsource (lib "eagle-import") (part "C-EUC0603"))
    )
    (comp (ref "C61")
      (value "100n")
      (footprint "eagle-import:C0603")
      (libsource (lib "eagle-import") (part "C-EUC0603"))
    )
    (comp (ref "C62")
      (value "100n")
      (footprint "eagle-import:C0603")
      (libsource (lib "eagle-import") (part "C-EUC0603"))
    )
    (comp (ref "C63")
      (value "1n")
      (footprint "eagle-import:C0805")
      (libsource (lib "eagle-import") (part "C-EUC0805"))
    )
    (comp (ref "C64")
      (value "1n")
      (footprint "eagle-import:C0805")
      (libsource (lib "eagle-import") (part "C-EUC0805"))
    )
    (comp (ref "D11")
      (value "BAS316")
      (footprint "eagle-import:SOD323-W")
      (libsource (lib "eagle-import") (part "DIODE-SOD323-W"))
    )
    (comp (ref "D12")
      (value "BAS316")
      (footprint "eagle-import:SOD323-W")
      (libsource (lib "eagle-import") (part "DIODE-SOD323-W"))
    )
    (comp (ref "D13")
      (value "BAS316")
      (footprint "eagle-import:SOD323-W")
      (libsource (lib "eagle-import") (part "DIODE-SOD323-W"))
    )
    (comp (ref "D14")
      (value "BAS316")
      (footprint "eagle-import:SOD323-W")
      (libsource (lib "eagle-import") (part "DIODE-SOD323-W"))
    )
    (comp (ref "D15")
      (value "BAS316")
      (footprint "eagle-import:SOD323-W")
      (libsource (lib "eagle-import") (part "DIODE-SOD323-W"))
    )
    (comp (ref "D16")
      (value "BAS316")
      (footprint "eagle-import:SOD323-W")
      (libsource (lib "eagle-import") (part "DIODE-SOD323-W"))
    )
    (comp (ref "D17")
      (value "BAS316")
      (footprint "eagle-import:SOD323-W")
      (libsource (lib "eagle-import") (part "DIODE-SOD323-W"))
    )
    (comp (ref "D18")
      (value "BAS316")
      (footprint "eagle-import:SOD323-W")
      (libsource (lib "eagle-import") (part "DIODE-SOD323-W"))
    )
    (comp (ref "IC6")
      (value "TL072D")
      (footprint "eagle-import:SOIC127P600X173-8N")
      (libsource (lib "eagle-import") (part "TL072SOIC8"))
    )
    (comp (ref "IC7")
      (value "TL072D")
      (footprint "eagle-import:SOIC127P600X173-8N")
      (libsource (lib "eagle-import") (part "TL072SOIC8"))
    )
    (comp (ref "IC8")
      (value "OP27GSZ")
      (footprint "eagle-import:SOIC127P600X173-8N")
      (libsource (lib "eagle-import") (part "OP27GSZSO8"))
    )
    (comp (ref "NTC1")
      (value "10K/Beta:3570K")
      (footprint "eagle-import:R_0204_5+0805")
      (libsource (lib "eagle-import") (part "NTC0805"))
    )
    (comp (ref "Q4")
      (value "IRFP250N")
      (footprint "eagle-import:TO247BH-CLR")
      (libsource (lib "eagle-import") (part "IRFP240BOTTOM"))
    )
    (comp (ref "Q5")
      (value "BC857C")
      (footprint "eagle-import:SOT23-BEC")
      (libsource (lib "eagle-import") (part "-PNP-SOT23-BECBC857C"))
    )
    (comp (ref "Q6")
      (value "BC846C")
      (footprint "eagle-import:SOT23-BEC")
      (libsource (lib "eagle-import") (part "-NPN-SOT23-BECBC846B"))
    )
    (comp (ref "Q7")
      (value "BCP56-16.115")
      (footprint "eagle-import:SOT230P700X180-4N")
      (libsource (lib "eagle-import") (part "BCP56"))
    )
    (comp (ref "Q8")
      (value "IRFR5410")
      (footprint "eagle-import:TO229P990X239-3N")
      (libsource (lib "eagle-import") (part "P-MOSFETDPAK"))
    )
    (comp (ref "Q9")
      (value "BCP56-16.115")
      (footprint "eagle-import:SOT230P700X180-4N")
      (libsource (lib "eagle-import") (part "BCP56"))
    )
    (comp (ref "Q10")
      (value "MMBT5401")
      (footprint "eagle-import:SOT23-BEC")
      (libsource (lib "eagle-import") (part "-PNP-SOT23-BECBC857B"))
    )
    (comp (ref "Q11")
      (value "MMBT5401")
      (footprint "eagle-import:SOT23-BEC")
      (libsource (lib "eagle-import") (part "-PNP-SOT23-BECBC857B"))
    )
    (comp (ref "Q12")
      (value "MMBT5551")
      (footprint "eagle-import:SOT23-BEC")
      (libsource (lib "eagle-import") (part "-NPN-SOT23-BECMMBT5551LT1"))
    )
    (comp (ref "Q13")
      (value "MMBT5551")
      (footprint "eagle-import:SOT23-BEC")
      (libsource (lib "eagle-import") (part "-NPN-SOT23-BECMMBT5551LT1"))
    )
    (comp (ref "R30")
      (value "R080/3W")
      (footprint "eagle-import:R2512")
      (libsource (lib "eagle-import") (part "R-EU_R2512"))
    )
    (comp (ref "R31")
      (value "2R2/2W")
      (footprint "eagle-import:R2512")
      (libsource (lib "eagle-import") (part "R-EU_R2512"))
    )
    (comp (ref "R32")
      (value "2K2")
      (footprint "eagle-import:R0805")
      (libsource (lib "eagle-import") (part "R-EU_R0805"))
    )
    (comp (ref "R33")
      (value "1K")
      (footprint "eagle-import:R0805")
      (libsource (lib "eagle-import") (part "R-EU_R0805"))
    )
    (comp (ref "R34")
      (value "2K2")
      (footprint "eagle-import:R0805")
      (libsource (lib "eagle-import") (part "R-EU_R0805"))
    )
    (comp (ref "R35")
      (value "2K2")
      (footprint "eagle-import:R0805")
      (libsource (lib "eagle-import") (part "R-EU_R0805"))
    )
    (comp (ref "R36")
      (value "16K")
      (footprint "eagle-import:R0805")
      (libsource (lib "eagle-import") (part "R-EU_R0805"))
    )
    (comp (ref "R37")
      (value "2K2")
      (footprint "eagle-import:R0805")
      (libsource (lib "eagle-import") (part "R-EU_R0805"))
    )
    (comp (ref "R38")
      (value "220R")
      (footprint "eagle-import:R0805")
      (libsource (lib "eagle-import") (part "R-EU_R0805"))
    )
    (comp (ref "R39")
      (value "220R")
      (footprint "eagle-import:R0805")
      (libsource (lib "eagle-import") (part "R-EU_R0805"))
    )
    (comp (ref "R40")
      (value "470R")
      (footprint "eagle-import:R0805")
      (libsource (lib "eagle-import") (part "R-EU_R0805"))
    )
    (comp (ref "R41")
      (value "1K")
      (footprint "eagle-import:R0805")
      (libsource (lib "eagle-import") (part "R-EU_R0805"))
    )
    (comp (ref "R42")
      (value "220R")
      (footprint "eagle-import:R0805")
      (libsource (lib "eagle-import") (part "R-EU_R0805"))
    )
    (comp (ref "R43")
      (value "100R")
      (footprint "eagle-import:R0805")
      (libsource (lib "eagle-import") (part "R-EU_R0805"))
    )
    (comp (ref "R44")
      (value "7K5 0.1%")
      (footprint "eagle-import:R0805")
      (libsource (lib "eagle-import") (part "R-EU_R0805"))
    )
    (comp (ref "R45")
      (value "10K")
      (footprint "eagle-import:R0805")
      (libsource (lib "eagle-import") (part "R-EU_R0805"))
    )
    (comp (ref "R46")
      (value "2K2")
      (footprint "eagle-import:R0805")
      (libsource (lib "eagle-import") (part "R-EU_R0805"))
    )
    (comp (ref "R47")
      (value "750R")
      (footprint "eagle-import:R0805")
      (libsource (lib "eagle-import") (part "R-EU_R0805"))
    )
    (comp (ref "R48")
      (value "220R")
      (footprint "eagle-import:R0805")
      (libsource (lib "eagle-import") (part "R-EU_R0805"))
    )
    (comp (ref "R49")
      (value "100K 0.1%")
      (footprint "eagle-import:R0805")
      (libsource (lib "eagle-import") (part "R-EU_R0805"))
    )
    (comp (ref "R50")
      (value "20K 0.1%")
      (footprint "eagle-import:R0805")
      (libsource (lib "eagle-import") (part "R-EU_R0805"))
    )
    (comp (ref "R51")
      (value "51K")
      (footprint "eagle-import:R0805")
      (libsource (lib "eagle-import") (part "R-EU_R0805"))
    )
    (comp (ref "R52")
      (value "10K")
      (footprint "eagle-import:R0805")
      (libsource (lib "eagle-import") (part "R-EU_R0805"))
    )
    (comp (ref "R53")
      (value "470R")
      (footprint "eagle-import:R0805")
      (libsource (lib "eagle-import") (part "R-EU_R0805"))
    )
    (comp (ref "R54")
      (value "10K")
      (footprint "eagle-import:R0805")
      (libsource (lib "eagle-import") (part "R-EU_R0805"))
    )
    (comp (ref "R55")
      (value "7K5 0.1%")
      (footprint "eagle-import:R0805")
      (libsource (lib "eagle-import") (part "R-EU_R0805"))
    )
    (comp (ref "R56")
      (value "1K8")
      (footprint "eagle-import:R0805")
      (libsource (lib "eagle-import") (part "R-EU_R0805"))
    )
    (comp (ref "R57")
      (value "0R")
      (footprint "eagle-import:R0805")
      (libsource (lib "eagle-import") (part "R-EU_R0805"))
    )
    (comp (ref "R58")
      (value "220R")
      (footprint "eagle-import:R0805")
      (libsource (lib "eagle-import") (part "R-EU_R0805"))
    )
    (comp (ref "R59")
      (value "100K 0.1%")
      (footprint "eagle-import:R0805")
      (libsource (lib "eagle-import") (part "R-EU_R0805"))
    )
    (comp (ref "R60")
      (value "20K 0.1%")
      (footprint "eagle-import:R0805")
      (libsource (lib "eagle-import") (part "R-EU_R0805"))
    )
    (comp (ref "R61")
      (value "10K")
      (footprint "eagle-import:R0805")
      (libsource (lib "eagle-import") (part "R-EU_R0805"))
    )
    (comp (ref "R62")
      (value "2K2")
      (footprint "eagle-import:R0805")
      (libsource (lib "eagle-import") (part "R-EU_R0805"))
    )
    (comp (ref "R63")
      (value "180R 0.1%")
      (footprint "eagle-import:R0805")
      (libsource (lib "eagle-import") (part "R-EU_R0805"))
    )
    (comp (ref "R64")
      (value "2K37 0.1%")
      (footprint "eagle-import:R0805")
      (libsource (lib "eagle-import") (part "R-EU_R0805"))
    )
    (comp (ref "R65")
      (value "2K2")
      (footprint "eagle-import:R0805")
      (libsource (lib "eagle-import") (part "R-EU_R0805"))
    )
    (comp (ref "R66")
      (value "51R 0.1%")
      (footprint "eagle-import:R0805")
      (libsource (lib "eagle-import") (part "R-EU_R0805"))
    )
    (comp (ref "R67")
      (value "51R 0.1%")
      (footprint "eagle-import:R0805")
      (libsource (lib "eagle-import") (part "R-EU_R0805"))
    )
    (comp (ref "R68")
      (value "2K2")
      (footprint "eagle-import:R0805")
      (libsource (lib "eagle-import") (part "R-EU_R0805"))
    )
    (comp (ref "R69")
      (value "R020/2W")
      (footprint "eagle-import:R2512")
      (libsource (lib "eagle-import") (part "R-EU_R2512"))
    )
    (comp (ref "R70")
      (value "51R 0.1%")
      (footprint "eagle-import:R0805")
      (libsource (lib "eagle-import") (part "R-EU_R0805"))
    )
    (comp (ref "R71")
      (value "51R 0.1%")
      (footprint "eagle-import:R0805")
      (libsource (lib "eagle-import") (part "R-EU_R0805"))
    )
    (comp (ref "R72")
      (value "2K37 0.1%")
      (footprint "eagle-import:R0805")
      (libsource (lib "eagle-import") (part "R-EU_R0805"))
    )
    (comp (ref "R73")
      (value "180R 0.1%")
      (footprint "eagle-import:R0805")
      (libsource (lib "eagle-import") (part "R-EU_R0805"))
    )
    (comp (ref "R74")
      (value "1K")
      (footprint "eagle-import:R0805")
      (libsource (lib "eagle-import") (part "R-EU_R0805"))
    )
    (comp (ref "R75")
      (value "10K")
      (footprint "eagle-import:R0805")
      (libsource (lib "eagle-import") (part "R-EU_R0805"))
    )
    (comp (ref "R76")
      (value "10K")
      (footprint "eagle-import:R0805")
      (libsource (lib "eagle-import") (part "R-EU_R0805"))
    )
    (comp (ref "TP1")
      (value "TEST_POINT")
      (footprint "eagle-import:TP_1.1MM")
      (libsource (lib "eagle-import") (part "TEST_POINT"))
    )
    (comp (ref "ZD3")
      (value "See Note 3.2")
      (footprint "eagle-import:DO214AA")
      (libsource (lib "eagle-import") (part "P6SMB68A"))
    )
    (comp (ref "ZD4")
      (value "BZX384-C15.115")
      (footprint "eagle-import:SOD323-W")
      (libsource (lib "eagle-import") (part "ZENER-DIODESOD323"))
    )
    (comp (ref "ZD5")
      (value "PDZ6.2B")
      (footprint "eagle-import:SOD323-W")
      (libsource (lib "eagle-import") (part "ZENER-DIODESOD323"))
    )
  )
  (nets
    (net (code "1") (name "+5V") (class "Default")
      (node (ref "C65") (pin "1") (pinfunction "1_1") (pintype "passive"))
      (node (ref "C73") (pin "2") (pinfunction "2_2") (pintype "passive"))
      (node (ref "C74") (pin "2") (pinfunction "2_2") (pintype "passive"))
      (node (ref "FB3") (pin "P$2") (pinfunction "2_P$2") (pintype "passive"))
      (node (ref "IC14") (pin "13") (pinfunction "DVDD_13") (pintype "power_in"))
      (node (ref "IC9") (pin "18") (pinfunction "VDD_18") (pintype "power_in"))
      (node (ref "Q13") (pin "B") (pinfunction "B_B") (pintype "passive"))
      (node (ref "Q14") (pin "2") (pinfunction "S_2") (pintype "passive"))
      (node (ref "R101") (pin "2") (pinfunction "2_2") (pintype "passive"))
      (node (ref "R77") (pin "1") (pinfunction "1_1") (pintype "passive"))
      (node (ref "R88") (pin "2") (pinfunction "2_2") (pintype "passive"))
      (node (ref "R98") (pin "2") (pinfunction "2_2") (pintype "passive"))
      (node (ref "X3") (pin "2") (pinfunction "1_2") (pintype "passive"))
    )
    (net (code "2") (name "+VREF") (class "Default")
      (node (ref "C67") (pin "+") (pinfunction "+_+") (pintype "passive"))
      (node (ref "C70") (pin "2") (pinfunction "2_2") (pintype "passive"))
      (node (ref "C79") (pin "2") (pinfunction "2_2") (pintype "passive"))
      (node (ref "IC10") (pin "6") (pinfunction "VOUT_6") (pintype "output"))
      (node (ref "IC11") (pin "2") (pinfunction "VREF_2") (pintype "input"))
      (node (ref "IC14") (pin "9") (pinfunction "REFP0_9") (pintype "input"))
    )
    (net (code "3") (name "-9V") (class "Default")
      (node (ref "C25") (pin "2") (pinfunction "2_2") (pintype "passive"))
      (node (ref "C27") (pin "2") (pinfunction "-_2") (pintype "passive"))
      (node (ref "IC2") (pin "2") (pinfunction "IN_2") (pintype "input"))
      (node (ref "IC2") (pin "3") (pinfunction "IN_3") (pintype "input"))
      (node (ref "IC2") (pin "6") (pinfunction "IN_6") (pintype "input"))
      (node (ref "IC2") (pin "7") (pinfunction "IN_7") (pintype "input"))
      (node (ref "L5") (pin "2") (pinfunction "2_2") (pintype "passive"))
      (node (ref "R41") (pin "2") (pinfunction "2_2") (pintype "passive"))
      (node (ref "R42") (pin "2") (pinfunction "2_2") (pintype "passive"))
    )
    (net (code "4") (name "AC_IN1") (class "Default")
      (node (ref "D3") (pin "3") (pinfunction "C_3") (pintype "passive"))
      (node (ref "D4") (pin "1") (pinfunction "A1_1") (pintype "passive"))
      (node (ref "D4") (pin "2") (pinfunction "A2_2") (pintype "passive"))
      (node (ref "X2") (pin "1") (pinfunction "1_1") (pintype "bidirectional"))
      (node (ref "ZD2") (pin "A") (pinfunction "2_A") (pintype "passive"))
    )
    (net (code "5") (name "AC_IN2") (class "Default")
      (node (ref "D1") (pin "3") (pinfunction "C_3") (pintype "passive"))
      (node (ref "D2") (pin "1") (pinfunction "A1_1") (pintype "passive"))
      (node (ref "D2") (pin "2") (pinfunction "A2_2") (pintype "passive"))
      (node (ref "X2") (pin "2") (pinfunction "1_2") (pintype "bidirectional"))
      (node (ref "ZD2") (pin "C") (pinfunction "1_C") (pintype "passive"))
    )
    (net (code "6") (name "AUX_USET_IN") (class "Default")
      (node (ref "R82") (pin "2") (pinfunction "2_2") (pintype "passive"))
      (node (ref "X3") (pin "11") (pinfunction "1_11") (pintype "passive"))
    )
    (net (code "7") (name "AUX_USET_SW") (class "Default")
      (node (ref "IC13") (pin "1") (pinfunction "IN_1") (pintype "input"))
      (node (ref "IC9") (pin "14") (pinfunction "GP4_14") (pintype "bidirectional"))
    )
    (net (code "8") (name "CC_ACTIVE") (class "Default")
      (node (ref "IC9") (pin "12") (pinfunction "GP2_12") (pintype "bidirectional"))
      (node (ref "R101") (pin "1") (pinfunction "1_1") (pintype "passive"))
      (node (ref "R104") (pin "2") (pinfunction "2_2") (pintype "passive"))
    )
    (net (code "9") (name "CS_ADC") (class "Default")
      (node (ref "IC14") (pin "2") (pinfunction "~{CS}_2") (pintype "input"))
      (node (ref "X3") (pin "6") (pinfunction "1_6") (pintype "passive"))
    )
    (net (code "10") (name "CS_DAC") (class "Default")
      (node (ref "IC11") (pin "5") (pinfunction "~{SYNC}_5") (pintype "input"))
      (node (ref "X3") (pin "4") (pinfunction "1_4") (pintype "passive"))
    )
    (net (code "11") (name "CS_EXPANDER") (class "Default")
      (node (ref "IC9") (pin "7") (pinfunction "~{CS}_7") (pintype "input"))
      (node (ref "X3") (pin "3") (pinfunction "1_3") (pintype "passive"))
    )
    (net (code "12") (name "CV_ACTIVE") (class "Default")
      (node (ref "IC9") (pin "15") (pinfunction "GP5_15") (pintype "bidirectional"))
      (node (ref "R88") (pin "1") (pinfunction "1_1") (pintype "passive"))
      (node (ref "R92") (pin "2") (pinfunction "2_2") (pintype "passive"))
    )
    (net (code "13") (name "DC+") (class "Default")
      (node (ref "C2") (pin "2") (pinfunction "2_2") (pintype "passive"))
      (node (ref "L1") (pin "2") (pinfunction "1_2") (pintype "passive"))
      (node (ref "X1") (pin "1") (pinfunction "1_1") (pintype "passive"))
      (node (ref "ZD1") (pin "C") (pinfunction "1_C") (pintype "passive"))
    )
    (net (code "14") (name "DC-") (class "Default")
      (node (ref "C2") (pin "1") (pinfunction "1_1") (pintype "passive"))
      (node (ref "L1") (pin "1") (pinfunction "1_1") (pintype "passive"))
      (node (ref "X1") (pin "2") (pinfunction "1_2") (pintype "passive"))
      (node (ref "ZD1") (pin "A") (pinfunction "2_A") (pintype "passive"))
    )
    (net (code "15") (name "DC_OUT") (class "Default")
      (node (ref "C1") (pin "2") (pinfunction "2_2") (pintype "passive"))
      (node (ref "C10") (pin "1") (pinfunction "1_1") (pintype "passive"))
      (node (ref "C4") (pin "+") (pinfunction "+_+") (pintype "passive"))
      (node (ref "C44") (pin "1") (pinfunction "1_1") (pintype "passive"))
      (node (ref "C5") (pin "+") (pinfunction "+_+") (pintype "passive"))
      (node (ref "C6") (pin "1") (pinfunction "1_1") (pintype "passive"))
      (node (ref "C7") (pin "1") (pinfunction "1_1") (pintype "passive"))
      (node (ref "C8") (pin "1") (pinfunction "1_1") (pintype "passive"))
      (node (ref "C9") (pin "2") (pinfunction "2_2") (pintype "passive"))
      (node (ref "D2") (pin "3") (pinfunction "C_3") (pintype "passive"))
      (node (ref "D4") (pin "3") (pinfunction "C_3") (pintype "passive"))
      (node (ref "IC1") (pin "11") (pinfunction "VIN_11") (pintype "passive"))
      (node (ref "L1") (pin "3") (pinfunction "2_3") (pintype "passive"))
      (node (ref "L6") (pin "1") (pinfunction "1_1") (pintype "passive"))
      (node (ref "Q7") (pin "2") (pinfunction "C_2") (pintype "passive"))
      (node (ref "Q7") (pin "4") (pinfunction "C_4") (pintype "passive"))
      (node (ref "R1") (pin "1") (pinfunction "1_1") (pintype "passive"))
      (node (ref "R2") (pin "1") (pinfunction "1_1") (pintype "passive"))
      (node (ref "R38") (pin "2") (pinfunction "2_2") (pintype "passive"))
      (node (ref "R39") (pin "2") (pinfunction "2_2") (pintype "passive"))
    )
    (net (code "16") (name "EARTH") (class "Default")
      (node (ref "C1") (pin "1") (pinfunction "1_1") (pintype "passive"))
      (node (ref "C3") (pin "2") (pinfunction "2_2") (pintype "passive"))
      (node (ref "X1") (pin "3") (pinfunction "1_3") (pintype "passive"))
    )
    (net (code "17") (name "GND") (class "Default")
      (node (ref "C10") (pin "2") (pinfunction "2_2") (pintype "passive"))
      (node (ref "C12") (pin "2") (pinfunction "2_2") (pintype "passive"))
      (node (ref "C18") (pin "2") (pinfunction "-_2") (pintype "passive"))
      (node (ref "C20") (pin "2") (pinfunction "2_2") (pintype "passive"))
      (node (ref "C24") (pin "2") (pinfunction "2_2") (pintype "passive"))
      (node (ref "C25") (pin "1") (pinfunction "1_1") (pintype "passive"))
      (node (ref "C26") (pin "1") (pinfunction "1_1") (pintype "passive"))
      (node (ref "C27") (pin "1") (pinfunction "+_1") (pintype "passive"))
      (node (ref "C28") (pin "2") (pinfunction "2_2") (pintype "passive"))
      (node (ref "C3") (pin "1") (pinfunction "1_1") (pintype "passive"))
      (node (ref "C30") (pin "2") (pinfunction "2_2") (pintype "passive"))
      (node (ref "C31") (pin "2") (pinfunction "2_2") (pintype "passive"))
      (node (ref "C32") (pin "2") (pinfunction "2_2") (pintype "passive"))
      (node (ref "C34") (pin "2") (pinfunction "2_2") (pintype "passive"))
      (node (ref "C35") (pin "2") (pinfunction "-_2") (pintype "passive"))
      (node (ref "C36") (pin "2") (pinfunction "2_2") (pintype "passive"))
      (node (ref "C37") (pin "1") (pinfunction "1_1") (pintype "passive"))
      (node (ref "C38") (pin "2") (pinfunction "2_2") (pintype "passive"))
      (node (ref "C39") (pin "2") (pinfunction "2_2") (pintype "passive"))
      (node (ref "C4") (pin "-") (pinfunction "-_-") (pintype "passive"))
      (node (ref "C40") (pin "1") (pinfunction "1_1") (pintype "passive"))
      (node (ref "C42") (pin "2") (pinfunction "2_2") (pintype "passive"))
      (node (ref "C43") (pin "-") (pinfunction "-_-") (pintype "passive"))
      (node (ref "C44") (pin "2") (pinfunction "2_2") (pintype "passive"))
      (node (ref "C45") (pin "2") (pinfunction "2_2") (pintype "passive"))
      (node (ref "C5") (pin "-") (pinfunction "-_-") (pintype "passive"))
      (node (ref "C53") (pin "1") (pinfunction "1_1") (pintype "passive"))
      (node (ref "C54") (pin "2") (pinfunction "2_2") (pintype "passive"))
      (node (ref "C55") (pin "1") (pinfunction "1_1") (pintype "passive"))
      (node (ref "C56") (pin "1") (pinfunction "1_1") (pintype "passive"))
      (node (ref "C57") (pin "1") (pinfunction "1_1") (pintype "passive"))
      (node (ref "C58") (pin "1") (pinfunction "1_1") (pintype "passive"))
      (node (ref "C59") (pin "1") (pinfunction "1_1") (pintype "passive"))
      (node (ref "C6") (pin "2") (pinfunction "2_2") (pintype "passive"))
      (node (ref "C60") (pin "2") (pinfunction "2_2") (pintype "passive"))
      (node (ref "C61") (pin "1") (pinfunction "1_1") (pintype "passive"))
      (node (ref "C62") (pin "1") (pinfunction "1_1") (pintype "passive"))
      (node (ref "C65") (pin "2") (pinfunction "2_2") (pintype "passive"))
      (node (ref "C66") (pin "2") (pinfunction "2_2") (pintype "passive"))
      (node (ref "C67") (pin "-") (pinfunction "-_-") (pintype "passive"))
      (node (ref "C68") (pin "2") (pinfunction "2_2") (pintype "passive"))
      (node (ref "C69") (pin "1") (pinfunction "1_1") (pintype "passive"))
      (node (ref "C7") (pin "2") (pinfunction "2_2") (pintype "passive"))
      (node (ref "C70") (pin "1") (pinfunction "1_1") (pintype "passive"))
      (node (ref "C71") (pin "1") (pinfunction "1_1") (pintype "passive"))
      (node (ref "C72") (pin "2") (pinfunction "2_2") (pintype "passive"))
      (node (ref "C73") (pin "1") (pinfunction "1_1") (pintype "passive"))
      (node (ref "C74") (pin "1") (pinfunction "1_1") (pintype "passive"))
      (node (ref "C75") (pin "1") (pinfunction "1_1") (pintype "passive"))
      (node (ref "C76") (pin "1") (pinfunction "1_1") (pintype "passive"))
      (node (ref "C77") (pin "1") (pinfunction "1_1") (pintype "passive"))
      (node (ref "C78") (pin "1") (pinfunction "1_1") (pintype "passive"))
      (node (ref "C79") (pin "1") (pinfunction "1_1") (pintype "passive"))
      (node (ref "C8") (pin "2") (pinfunction "2_2") (pintype "passive"))
      (node (ref "C82") (pin "1") (pinfunction "1_1") (pintype "passive"))
      (node (ref "C83") (pin "1") (pinfunction "1_1") (pintype "passive"))
      (node (ref "D1") (pin "1") (pinfunction "A1_1") (pintype "passive"))
      (node (ref "D1") (pin "2") (pinfunction "A2_2") (pintype "passive"))
      (node (ref "D3") (pin "1") (pinfunction "A1_1") (pintype "passive"))
      (node (ref "D3") (pin "2") (pinfunction "A2_2") (pintype "passive"))
      (node (ref "D5") (pin "1") (pinfunction "A_1") (pintype "passive"))
      (node (ref "D5") (pin "2") (pinfunction "A_2") (pintype "passive"))
      (node (ref "D8") (pin "C") (pinfunction "C_C") (pintype "passive"))
      (node (ref "D9") (pin "A") (pinfunction "A_A") (pintype "passive"))
      (node (ref "GND") (pin "P$1") (pinfunction "P$1_P$1") (pintype "bidirectional"))
      (node (ref "IC1") (pin "TP") (pinfunction "PGND_TP") (pintype "passive"))
      (node (ref "IC10") (pin "4") (pinfunction "GND_4") (pintype "passive"))
      (node (ref "IC11") (pin "8") (pinfunction "GND_8") (pintype "power_in"))
      (node (ref "IC13") (pin "3") (pinfunction "GND_3") (pintype "passive"))
      (node (ref "IC14") (pin "3") (pinfunction "CLK_3") (pintype "bidirectional"))
      (node (ref "IC14") (pin "4") (pinfunction "DGND_4") (pintype "power_in"))
      (node (ref "IC14") (pin "5") (pinfunction "AVSS_5") (pintype "power_in"))
      (node (ref "IC14") (pin "8") (pinfunction "REFN0_8") (pintype "input"))
      (node (ref "IC2") (pin "5") (pinfunction "GND_5") (pintype "passive"))
      (node (ref "IC3") (pin "2") (pinfunction "GND_2") (pintype "passive"))
      (node (ref "IC3") (pin "3") (pinfunction "GND_3") (pintype "passive"))
      (node (ref "IC3") (pin "6") (pinfunction "GND_6") (pintype "passive"))
      (node (ref "IC3") (pin "7") (pinfunction "GND_7") (pintype "passive"))
      (node (ref "IC4") (pin "12") (pinfunction "PGND_12") (pintype "passive"))
      (node (ref "IC4") (pin "9") (pinfunction "AGND_9") (pintype "passive"))
      (node (ref "IC5") (pin "4") (pinfunction "GND_4") (pintype "passive"))
      (node (ref "IC7") (pin "5") (pinfunction "+IN_5") (pintype "input"))
      (node (ref "IC9") (pin "4") (pinfunction "A1_4") (pintype "input"))
      (node (ref "IC9") (pin "5") (pinfunction "A0_5") (pintype "input"))
      (node (ref "IC9") (pin "9") (pinfunction "VSS_9") (pintype "power_in"))
      (node (ref "L1") (pin "4") (pinfunction "2_4") (pintype "passive"))
      (node (ref "Q15") (pin "2") (pinfunction "S_2") (pintype "passive"))
      (node (ref "Q16") (pin "E") (pinfunction "E_E") (pintype "passive"))
      (node (ref "Q18") (pin "E") (pinfunction "E_E") (pintype "passive"))
      (node (ref "Q8") (pin "2") (pinfunction "D_2") (pintype "passive"))
      (node (ref "R1") (pin "2") (pinfunction "2_2") (pintype "passive"))
      (node (ref "R103") (pin "1") (pinfunction "1_1") (pintype "passive"))
      (node (ref "R17") (pin "1") (pinfunction "1_1") (pintype "passive"))
      (node (ref "R20") (pin "2") (pinfunction "2_2") (pintype "passive"))
      (node (ref "R22") (pin "2") (pinfunction "2_2") (pintype "passive"))
      (node (ref "R27") (pin "2") (pinfunction "2_2") (pintype "passive"))
      (node (ref "R28") (pin "1") (pinfunction "1_1") (pintype "passive"))
      (node (ref "R44") (pin "1") (pinfunction "1_1") (pintype "passive"))
      (node (ref "R46") (pin "1") (pinfunction "1_1") (pintype "passive"))
      (node (ref "R47") (pin "1") (pinfunction "1_1") (pintype "passive"))
      (node (ref "R51") (pin "1") (pinfunction "1_1") (pintype "passive"))
      (node (ref "R63") (pin "1") (pinfunction "1_1") (pintype "passive"))
      (node (ref "R79") (pin "1") (pinfunction "1_1") (pintype "passive"))
      (node (ref "R8") (pin "1") (pinfunction "1_1") (pintype "passive"))
      (node (ref "R90") (pin "1") (pinfunction "1_1") (pintype "passive"))
      (node (ref "R94") (pin "1") (pinfunction "1_1") (pintype "passive"))
      (node (ref "R97") (pin "2") (pinfunction "2_2") (pintype "passive"))
      (node (ref "SH1") (pin "P$2") (pinfunction "GND_B_P$2") (pintype "bidirectional"))
      (node (ref "SH2") (pin "P$2") (pinfunction "GND_B_P$2") (pintype "bidirectional"))
      (node (ref "TP1") (pin "GND") (pinfunction "GND_GND") (pintype "bidirectional"))
      (node (ref "TR1") (pin "4") (pinfunction "4_4") (pintype "passive"))
      (node (ref "X3") (pin "10") (pinfunction "1_10") (pintype "passive"))
      (node (ref "X3") (pin "12") (pinfunction "1_12") (pintype "passive"))
      (node (ref "X3") (pin "14") (pinfunction "1_14") (pintype "passive"))
    )
    (net (code "18") (name "I_MON") (class "Default")
      (node (ref "IC8") (pin "6") (pinfunction "OUT_6") (pintype "output"))
      (node (ref "R68") (pin "1") (pinfunction "1_1") (pintype "passive"))
      (node (ref "R72") (pin "2") (pinfunction "2_2") (pintype "passive"))
      (node (ref "R84") (pin "1") (pinfunction "1_1") (pintype "passive"))
    )
    (net (code "19") (name "I_SERVO") (class "Default")
      (node (ref "C63") (pin "2") (pinfunction "2_2") (pintype "passive"))
      (node (ref "D17") (pin "C") (pinfunction "C_C") (pintype "passive"))
      (node (ref "D18") (pin "A") (pinfunction "A_A") (pintype "passive"))
      (node (ref "IC7") (pin "1") (pinfunction "OUT_1") (pintype "output"))
      (node (ref "R106") (pin "1") (pinfunction "1_1") (pintype "passive"))
    )
    (net (code "20") (name "I_SET") (class "Default")
      (node (ref "IC11") (pin "3") (pinfunction "VOUTB_3") (pintype "output"))
      (node (ref "R65") (pin "1") (pinfunction "1_1") (pintype "passive"))
      (node (ref "R80") (pin "1") (pinfunction "1_1") (pintype "passive"))
    )
    (net (code "21") (name "MCU_VCC") (class "Default")
      (node (ref "NTC1") (pin "2") (pinfunction "P$2_2") (pintype "bidirectional"))
      (node (ref "NTC1") (pin "2.1") (pinfunction "P$2_2.1") (pintype "bidirectional"))
      (node (ref "X3") (pin "15") (pinfunction "1_15") (pintype "passive"))
    )
    (net (code "22") (name "Net-(C13-Pad1)") (class "Default")
      (node (ref "C13") (pin "1") (pinfunction "1_1") (pintype "passive"))
      (node (ref "C19") (pin "2") (pinfunction "2_2") (pintype "passive"))
      (node (ref "L3") (pin "2") (pinfunction "2_2") (pintype "passive"))
      (node (ref "L4") (pin "1") (pinfunction "1_1") (pintype "passive"))
      (node (ref "R5") (pin "2") (pinfunction "2_2") (pintype "passive"))
      (node (ref "R6") (pin "1") (pinfunction "1_1") (pintype "passive"))
    )
    (net (code "23") (name "Net-(C17-Pad2)") (class "Default")
      (node (ref "C17") (pin "2") (pinfunction "2_2") (pintype "passive"))
      (node (ref "R8") (pin "2") (pinfunction "2_2") (pintype "passive"))
    )
    (net (code "24") (name "Net-(C18-+)") (class "Default")
      (node (ref "C12") (pin "1") (pinfunction "1_1") (pintype "passive"))
      (node (ref "C18") (pin "1") (pinfunction "+_1") (pintype "passive"))
      (node (ref "C20") (pin "1") (pinfunction "1_1") (pintype "passive"))
      (node (ref "L2") (pin "2") (pinfunction "2_2") (pintype "passive"))
      (node (ref "L3") (pin "1") (pinfunction "1_1") (pintype "passive"))
      (node (ref "R10") (pin "1") (pinfunction "1_1") (pintype "passive"))
      (node (ref "R11") (pin "1") (pinfunction "1_1") (pintype "passive"))
      (node (ref "R12") (pin "1") (pinfunction "1_1") (pintype "passive"))
      (node (ref "R5") (pin "1") (pinfunction "1_1") (pintype "passive"))
    )
    (net (code "25") (name "Net-(C22-Pad1)") (class "Default")
      (node (ref "C22") (pin "1") (pinfunction "1_1") (pintype "passive"))
      (node (ref "R9") (pin "1") (pinfunction "1_1") (pintype "passive"))
    )
    (net (code "26") (name "Net-(C23-Pad2)") (class "Default")
      (node (ref "C23") (pin "2") (pinfunction "2_2") (pintype "passive"))
      (node (ref "D6") (pin "A") (pinfunction "A_A") (pintype "passive"))
      (node (ref "Q2") (pin "B") (pinfunction "B_B") (pintype "passive"))
      (node (ref "R11") (pin "2") (pinfunction "2_2") (pintype "passive"))
      (node (ref "R14") (pin "1") (pinfunction "1_1") (pintype "passive"))
    )
    (net (code "27") (name "Net-(C24-Pad1)") (class "Default")
      (node (ref "C24") (pin "1") (pinfunction "1_1") (pintype "passive"))
      (node (ref "D7") (pin "A") (pinfunction "A_A") (pintype "passive"))
      (node (ref "L5") (pin "1") (pinfunction "1_1") (pintype "passive"))
    )
    (net (code "28") (name "Net-(C33-Pad2)") (class "Default")
      (node (ref "C33") (pin "2") (pinfunction "2_2") (pintype "passive"))
      (node (ref "R18") (pin "2") (pinfunction "2_2") (pintype "passive"))
    )
    (net (code "29") (name "Net-(C35-+)") (class "Default")
      (node (ref "C35") (pin "1") (pinfunction "+_1") (pintype "passive"))
      (node (ref "C38") (pin "1") (pinfunction "1_1") (pintype "passive"))
      (node (ref "C39") (pin "1") (pinfunction "1_1") (pintype "passive"))
      (node (ref "IC4") (pin "11") (pinfunction "OUT_11") (pintype "output"))
      (node (ref "L7") (pin "1") (pinfunction "1_1") (pintype "passive"))
      (node (ref "R19") (pin "1") (pinfunction "1_1") (pintype "passive"))
      (node (ref "TR1") (pin "3") (pinfunction "3_3") (pintype "passive"))
    )
    (net (code "30") (name "Net-(C41-Pad2)") (class "Default")
      (node (ref "C41") (pin "2") (pinfunction "2_2") (pintype "passive"))
      (node (ref "R24") (pin "2") (pinfunction "2_2") (pintype "passive"))
    )
    (net (code "31") (name "Net-(C45-Pad1)") (class "Default")
      (node (ref "C45") (pin "1") (pinfunction "1_1") (pintype "passive"))
      (node (ref "R40") (pin "1") (pinfunction "1_1") (pintype "passive"))
    )
    (net (code "32") (name "Net-(C46-Pad2)") (class "Default")
      (node (ref "C46") (pin "2") (pinfunction "2_2") (pintype "passive"))
      (node (ref "R45") (pin "1") (pinfunction "1_1") (pintype "passive"))
    )
    (net (code "33") (name "Net-(C47-Pad2)") (class "Default")
      (node (ref "C47") (pin "2") (pinfunction "2_2") (pintype "passive"))
      (node (ref "R48") (pin "1") (pinfunction "1_1") (pintype "passive"))
    )
    (net (code "34") (name "Net-(C48-Pad1)") (class "Default")
      (node (ref "C48") (pin "1") (pinfunction "1_1") (pintype "passive"))
      (node (ref "R49") (pin "2") (pinfunction "2_2") (pintype "passive"))
      (node (ref "R50") (pin "1") (pinfunction "1_1") (pintype "passive"))
    )
    (net (code "35") (name "Net-(C49-Pad1)") (class "Default")
      (node (ref "C49") (pin "1") (pinfunction "1_1") (pintype "passive"))
      (node (ref "R59") (pin "2") (pinfunction "2_2") (pintype "passive"))
      (node (ref "R60") (pin "1") (pinfunction "1_1") (pintype "passive"))
    )
    (net (code "36") (name "Net-(C50-Pad2)") (class "Default")
      (node (ref "C50") (pin "2") (pinfunction "2_2") (pintype "passive"))
      (node (ref "R57") (pin "1") (pinfunction "1_1") (pintype "passive"))
    )
    (net (code "37") (name "Net-(C51-Pad2)") (class "Default")
      (node (ref "C51") (pin "2") (pinfunction "2_2") (pintype "passive"))
      (node (ref "R58") (pin "1") (pinfunction "1_1") (pintype "passive"))
    )
    (net (code "38") (name "Net-(C52-Pad2)") (class "Default")
      (node (ref "C52") (pin "2") (pinfunction "2_2") (pintype "passive"))
      (node (ref "R61") (pin "1") (pinfunction "1_1") (pintype "passive"))
    )
    (net (code "39") (name "Net-(C63-Pad1)") (class "Default")
      (node (ref "C63") (pin "1") (pinfunction "1_1") (pintype "passive"))
      (node (ref "R74") (pin "1") (pinfunction "1_1") (pintype "passive"))
    )
    (net (code "40") (name "Net-(C64-Pad2)") (class "Default")
      (node (ref "C64") (pin "2") (pinfunction "2_2") (pintype "passive"))
      (node (ref "R76") (pin "1") (pinfunction "1_1") (pintype "passive"))
    )
    (net (code "41") (name "Net-(C80-Pad2)") (class "Default")
      (node (ref "C80") (pin "2") (pinfunction "2_2") (pintype "passive"))
      (node (ref "Q17") (pin "B") (pinfunction "B_B") (pintype "passive"))
      (node (ref "R87") (pin "1") (pinfunction "1_1") (pintype "passive"))
      (node (ref "R93") (pin "2") (pinfunction "2_2") (pintype "passive"))
      (node (ref "R96") (pin "2") (pinfunction "2_2") (pintype "passive"))
    )
    (net (code "42") (name "Net-(C81-Pad1)") (class "Default")
      (node (ref "C81") (pin "1") (pinfunction "1_1") (pintype "passive"))
      (node (ref "Q16") (pin "B") (pinfunction "B_B") (pintype "passive"))
      (node (ref "R90") (pin "2") (pinfunction "2_2") (pintype "passive"))
      (node (ref "R91") (pin "2") (pinfunction "2_2") (pintype "passive"))
    )
    (net (code "43") (name "Net-(C81-Pad2)") (class "Default")
      (node (ref "C81") (pin "2") (pinfunction "2_2") (pintype "passive"))
      (node (ref "Q17") (pin "C") (pinfunction "C_C") (pintype "passive"))
      (node (ref "R91") (pin "1") (pinfunction "1_1") (pintype "passive"))
      (node (ref "R99") (pin "2") (pinfunction "2_2") (pintype "passive"))
    )
    (net (code "44") (name "Net-(C84-Pad1)") (class "Default")
      (node (ref "C84") (pin "1") (pinfunction "1_1") (pintype "passive"))
      (node (ref "Q19") (pin "B") (pinfunction "B_B") (pintype "passive"))
      (node (ref "R100") (pin "1") (pinfunction "1_1") (pintype "passive"))
      (node (ref "R105") (pin "2") (pinfunction "2_2") (pintype "passive"))
    )
    (net (code "45") (name "Net-(D5-C)") (class "Default")
      (node (ref "C17") (pin "1") (pinfunction "1_1") (pintype "passive"))
      (node (ref "D5") (pin "3") (pinfunction "C_3") (pintype "passive"))
      (node (ref "L2") (pin "1") (pinfunction "1_1") (pintype "passive"))
      (node (ref "Q1") (pin "2") (pinfunction "D_2") (pintype "passive"))
      (node (ref "R4") (pin "1") (pinfunction "1_1") (pintype "passive"))
    )
    (net (code "46") (name "Net-(D6-PadC)") (class "Default")
      (node (ref "D6") (pin "C") (pinfunction "C_C") (pintype "passive"))
      (node (ref "Q2") (pin "E") (pinfunction "E_E") (pintype "passive"))
      (node (ref "R10") (pin "2") (pinfunction "2_2") (pintype "passive"))
    )
    (net (code "47") (name "Net-(D7-PadC)") (class "Default")
      (node (ref "D7") (pin "C") (pinfunction "C_C") (pintype "passive"))
      (node (ref "TR1") (pin "2") (pinfunction "2_2") (pintype "passive"))
    )
    (net (code "48") (name "Net-(D11-PadC)") (class "Default")
      (node (ref "D11") (pin "C") (pinfunction "C_C") (pintype "passive"))
      (node (ref "D12") (pin "A") (pinfunction "A_A") (pintype "passive"))
      (node (ref "Q4") (pin "G") (pinfunction "G_G") (pintype "passive"))
      (node (ref "R32") (pin "1") (pinfunction "1_1") (pintype "passive"))
    )
    (net (code "49") (name "Net-(D12-PadC)") (class "Default")
      (node (ref "D12") (pin "C") (pinfunction "C_C") (pintype "passive"))
      (node (ref "ZD5") (pin "C") (pinfunction "C_C") (pintype "passive"))
    )
    (net (code "50") (name "Net-(D13-PadC)") (class "Default")
      (node (ref "D13") (pin "C") (pinfunction "C_C") (pintype "passive"))
      (node (ref "Q9") (pin "2") (pinfunction "C_2") (pintype "passive"))
      (node (ref "Q9") (pin "4") (pinfunction "C_4") (pintype "passive"))
      (node (ref "ZD5") (pin "A") (pinfunction "A_A") (pintype "passive"))
    )
    (net (code "51") (name "Net-(D14-PadC)") (class "Default")
      (node (ref "D14") (pin "C") (pinfunction "C_C") (pintype "passive"))
      (node (ref "Q6") (pin "C") (pinfunction "C_C") (pintype "passive"))
      (node (ref "ZD4") (pin "C") (pinfunction "C_C") (pintype "passive"))
    )
    (net (code "52") (name "Net-(D15-PadA)") (class "Default")
      (node (ref "D15") (pin "A") (pinfunction "A_A") (pintype "passive"))
      (node (ref "D17") (pin "A") (pinfunction "A_A") (pintype "passive"))
      (node (ref "R53") (pin "1") (pinfunction "1_1") (pintype "passive"))
    )
    (net (code "53") (name "Net-(FB1-1)") (class "Default")
      (node (ref "C26") (pin "2") (pinfunction "2_2") (pintype "passive"))
      (node (ref "D8") (pin "A") (pinfunction "A_A") (pintype "passive"))
      (node (ref "FB1") (pin "P$1") (pinfunction "1_P$1") (pintype "passive"))
      (node (ref "IC2") (pin "1") (pinfunction "OUT_1") (pintype "passive"))
    )
    (net (code "54") (name "Net-(FB2-1)") (class "Default")
      (node (ref "C30") (pin "1") (pinfunction "1_1") (pintype "passive"))
      (node (ref "D9") (pin "C") (pinfunction "C_C") (pintype "passive"))
      (node (ref "FB2") (pin "P$1") (pinfunction "1_P$1") (pintype "passive"))
      (node (ref "IC3") (pin "1") (pinfunction "VO_1") (pintype "passive"))
    )
    (net (code "55") (name "Net-(FB3-1)") (class "Default")
      (node (ref "C43") (pin "+") (pinfunction "+_+") (pintype "passive"))
      (node (ref "FB3") (pin "P$1") (pinfunction "1_P$1") (pintype "passive"))
      (node (ref "IC5") (pin "1") (pinfunction "OUT_1") (pintype "output"))
      (node (ref "R25") (pin "1") (pinfunction "1_1") (pintype "passive"))
      (node (ref "R29") (pin "1") (pinfunction "1_1") (pintype "passive"))
    )
    (net (code "56") (name "Net-(IC1-CAP)") (class "Default")
      (node (ref "C9") (pin "1") (pinfunction "1_1") (pintype "passive"))
      (node (ref "IC1") (pin "9") (pinfunction "CAP_9") (pintype "passive"))
    )
    (net (code "57") (name "Net-(IC1-FREQ)") (class "Default")
      (node (ref "IC1") (pin "2") (pinfunction "FREQ_2") (pintype "input"))
      (node (ref "R7") (pin "1") (pinfunction "1_1") (pintype "passive"))
    )
    (net (code "58") (name "Net-(IC1-GATE)") (class "Default")
      (node (ref "IC1") (pin "12") (pinfunction "GATE_12") (pintype "output"))
      (node (ref "Q1") (pin "1") (pinfunction "G_1") (pintype "passive"))
    )
    (net (code "59") (name "Net-(IC1-ITH)") (class "Default")
      (node (ref "C21") (pin "1") (pinfunction "1_1") (pintype "passive"))
      (node (ref "IC1") (pin "6") (pinfunction "ITH_6") (pintype "bidirectional"))
      (node (ref "R9") (pin "2") (pinfunction "2_2") (pintype "passive"))
    )
    (net (code "60") (name "Net-(IC1-PLLIN{slash}MODE)") (class "Default")
      (node (ref "IC1") (pin "1") (pinfunction "PLLIN/MODE_1") (pintype "input"))
      (node (ref "JP1") (pin "2") (pinfunction "2_2") (pintype "passive"))
    )
    (net (code "61") (name "Net-(IC1-RUN)") (class "Default")
      (node (ref "IC1") (pin "8") (pinfunction "RUN_8") (pintype "input"))
      (node (ref "R3") (pin "1") (pinfunction "1_1") (pintype "passive"))
    )
    (net (code "62") (name "Net-(IC1-SENSE)") (class "Default")
      (node (ref "IC1") (pin "10") (pinfunction "SENSE_10") (pintype "input"))
      (node (ref "Q1") (pin "3") (pinfunction "S_3") (pintype "passive"))
      (node (ref "R2") (pin "2") (pinfunction "2_2") (pintype "passive"))
    )
    (net (code "63") (name "Net-(IC1-SS)") (class "Default")
      (node (ref "C11") (pin "2") (pinfunction "2_2") (pintype "passive"))
      (node (ref "IC1") (pin "4") (pinfunction "SS_4") (pintype "input"))
    )
    (net (code "64") (name "Net-(IC1-VFB)") (class "Default")
      (node (ref "IC1") (pin "5") (pinfunction "VFB_5") (pintype "input"))
      (node (ref "Q3") (pin "2") (pinfunction "S_2") (pintype "passive"))
      (node (ref "R12") (pin "2") (pinfunction "2_2") (pintype "passive"))
      (node (ref "R13") (pin "2") (pinfunction "2_2") (pintype "passive"))
      (node (ref "R15") (pin "1") (pinfunction "1_1") (pintype "passive"))
    )
    (net (code "65") (name "Net-(IC3-VI)") (class "Default")
      (node (ref "C32") (pin "1") (pinfunction "1_1") (pintype "passive"))
      (node (ref "C36") (pin "1") (pinfunction "1_1") (pintype "passive"))
      (node (ref "C42") (pin "1") (pinfunction "1_1") (pintype "passive"))
      (node (ref "IC3") (pin "8") (pinfunction "VI_8") (pintype "input"))
      (node (ref "IC5") (pin "8") (pinfunction "IN_8") (pintype "power_in"))
      (node (ref "L7") (pin "2") (pinfunction "2_2") (pintype "passive"))
      (node (ref "LED1") (pin "A") (pinfunction "A_A") (pintype "passive"))
    )
    (net (code "66") (name "Net-(IC4-BST)") (class "Default")
      (node (ref "C29") (pin "2") (pinfunction "2_2") (pintype "passive"))
      (node (ref "IC4") (pin "16") (pinfunction "BST_16") (pintype "input"))
    )
    (net (code "67") (name "Net-(IC4-COMP)") (class "Default")
      (node (ref "IC4") (pin "5") (pinfunction "COMP_5") (pintype "input"))
      (node (ref "R24") (pin "1") (pinfunction "1_1") (pintype "passive"))
    )
    (net (code "68") (name "Net-(IC4-FB)") (class "Default")
      (node (ref "C41") (pin "1") (pinfunction "1_1") (pintype "passive"))
      (node (ref "IC4") (pin "6") (pinfunction "FB_6") (pintype "input"))
      (node (ref "R19") (pin "2") (pinfunction "2_2") (pintype "passive"))
      (node (ref "R26") (pin "1") (pinfunction "1_1") (pintype "passive"))
    )
    (net (code "69") (name "Net-(IC4-IS)") (class "Default")
      (node (ref "D10") (pin "A") (pinfunction "A_A") (pintype "passive"))
      (node (ref "IC4") (pin "13") (pinfunction "IS_13") (pintype "input"))
      (node (ref "R18") (pin "1") (pinfunction "1_1") (pintype "passive"))
    )
    (net (code "70") (name "Net-(IC4-PRE)") (class "Default")
      (node (ref "C29") (pin "1") (pinfunction "1_1") (pintype "passive"))
      (node (ref "C33") (pin "1") (pinfunction "1_1") (pintype "passive"))
      (node (ref "D10") (pin "C") (pinfunction "C_C") (pintype "passive"))
      (node (ref "IC4") (pin "14") (pinfunction "SW_14") (pintype "output"))
      (node (ref "IC4") (pin "15") (pinfunction "PRE_15") (pintype "input"))
      (node (ref "TR1") (pin "1") (pinfunction "1_1") (pintype "passive"))
    )
    (net (code "71") (name "Net-(IC4-RAMP)") (class "Default")
      (node (ref "C40") (pin "2") (pinfunction "2_2") (pintype "passive"))
      (node (ref "IC4") (pin "8") (pinfunction "RAMP_8") (pintype "input"))
    )
    (net (code "72") (name "Net-(IC4-RT)") (class "Default")
      (node (ref "IC4") (pin "7") (pinfunction "RT_7") (pintype "input"))
      (node (ref "R23") (pin "1") (pinfunction "1_1") (pintype "passive"))
    )
    (net (code "73") (name "Net-(IC4-SD)") (class "Default")
      (node (ref "IC4") (pin "2") (pinfunction "SD_2") (pintype "input"))
      (node (ref "R16") (pin "1") (pinfunction "1_1") (pintype "passive"))
      (node (ref "R17") (pin "2") (pinfunction "2_2") (pintype "passive"))
    )
    (net (code "74") (name "Net-(IC4-SS)") (class "Default")
      (node (ref "C34") (pin "1") (pinfunction "1_1") (pintype "passive"))
      (node (ref "IC4") (pin "10") (pinfunction "SS_10") (pintype "input"))
    )
    (net (code "75") (name "Net-(IC4-VCC)") (class "Default")
      (node (ref "C37") (pin "2") (pinfunction "2_2") (pintype "passive"))
      (node (ref "IC4") (pin "1") (pinfunction "VCC_1") (pintype "power_in"))
    )
    (net (code "76") (name "Net-(IC4-VIN)") (class "Default")
      (node (ref "C28") (pin "1") (pinfunction "1_1") (pintype "passive"))
      (node (ref "C31") (pin "1") (pinfunction "1_1") (pintype "passive"))
      (node (ref "IC4") (pin "3") (pinfunction "VIN_3") (pintype "input"))
      (node (ref "L6") (pin "2") (pinfunction "2_2") (pintype "passive"))
      (node (ref "R16") (pin "2") (pinfunction "2_2") (pintype "passive"))
    )
    (net (code "77") (name "Net-(IC5-FB)") (class "Default")
      (node (ref "IC5") (pin "7") (pinfunction "FB_7") (pintype "input"))
      (node (ref "R25") (pin "2") (pinfunction "2_2") (pintype "passive"))
      (node (ref "R27") (pin "1") (pinfunction "1_1") (pintype "passive"))
    )
    (net (code "78") (name "Net-(IC6A-+IN)") (class "Default")
      (node (ref "IC6") (pin "3") (pinfunction "+IN_3") (pintype "input"))
      (node (ref "R48") (pin "2") (pinfunction "2_2") (pintype "passive"))
      (node (ref "R52") (pin "2") (pinfunction "2_2") (pintype "passive"))
    )
    (net (code "79") (name "Net-(IC6A--IN)") (class "Default")
      (node (ref "C50") (pin "1") (pinfunction "1_1") (pintype "passive"))
      (node (ref "D16") (pin "C") (pinfunction "C_C") (pintype "passive"))
      (node (ref "IC6") (pin "2") (pinfunction "-IN_2") (pintype "input"))
      (node (ref "R54") (pin "2") (pinfunction "2_2") (pintype "passive"))
      (node (ref "R58") (pin "2") (pinfunction "2_2") (pintype "passive"))
    )
    (net (code "80") (name "Net-(IC6B-+IN)") (class "Default")
      (node (ref "IC6") (pin "5") (pinfunction "+IN_5") (pintype "input"))
      (node (ref "R44") (pin "2") (pinfunction "2_2") (pintype "passive"))
      (node (ref "R45") (pin "2") (pinfunction "2_2") (pintype "passive"))
      (node (ref "R49") (pin "1") (pinfunction "1_1") (pintype "passive"))
    )
    (net (code "81") (name "Net-(IC6B--IN)") (class "Default")
      (node (ref "IC6") (pin "6") (pinfunction "-IN_6") (pintype "input"))
      (node (ref "R55") (pin "2") (pinfunction "2_2") (pintype "passive"))
      (node (ref "R59") (pin "1") (pinfunction "1_1") (pintype "passive"))
      (node (ref "R61") (pin "2") (pinfunction "2_2") (pintype "passive"))
    )
    (net (code "82") (name "Net-(IC7A-+IN)") (class "Default")
      (node (ref "IC7") (pin "3") (pinfunction "+IN_3") (pintype "input"))
      (node (ref "R65") (pin "2") (pinfunction "2_2") (pintype "passive"))
    )
    (net (code "83") (name "Net-(IC7A--IN)") (class "Default")
      (node (ref "D18") (pin "C") (pinfunction "C_C") (pintype "passive"))
      (node (ref "IC7") (pin "2") (pinfunction "-IN_2") (pintype "input"))
      (node (ref "R68") (pin "2") (pinfunction "2_2") (pintype "passive"))
      (node (ref "R75") (pin "2") (pinfunction "2_2") (pintype "passive"))
      (node (ref "R76") (pin "2") (pinfunction "2_2") (pintype "passive"))
    )
    (net (code "84") (name "Net-(IC7B--IN)") (class "Default")
      (node (ref "IC7") (pin "6") (pinfunction "-IN_6") (pintype "input"))
      (node (ref "IC7") (pin "7") (pinfunction "OUT_7") (pintype "output"))
    )
    (net (code "85") (name "Net-(IC8A-+IN)") (class "Default")
      (node (ref "IC8") (pin "3") (pinfunction "+IN_3") (pintype "input"))
      (node (ref "R64") (pin "2") (pinfunction "2_2") (pintype "passive"))
      (node (ref "R66") (pin "2") (pinfunction "2_2") (pintype "passive"))
    )
    (net (code "86") (name "Net-(IC8A--IN)") (class "Default")
      (node (ref "IC8") (pin "2") (pinfunction "-IN_2") (pintype "input"))
      (node (ref "R70") (pin "2") (pinfunction "2_2") (pintype "passive"))
      (node (ref "R73") (pin "1") (pinfunction "1_1") (pintype "passive"))
    )
    (net (code "87") (name "Net-(IC9-INT)") (class "Default")
      (node (ref "IC9") (pin "8") (pinfunction "INT_8") (pintype "output"))
      (node (ref "JP2") (pin "1") (pinfunction "1_1") (pintype "passive"))
    )
    (net (code "88") (name "Net-(IC10-TRIM{slash}NR)") (class "Default")
      (node (ref "C68") (pin "1") (pinfunction "1_1") (pintype "passive"))
      (node (ref "IC10") (pin "5") (pinfunction "TRIM/NR_5") (pintype "input"))
    )
    (net (code "89") (name "Net-(IC12-VD)") (class "Default")
      (node (ref "IC12") (pin "1") (pinfunction "VD_1") (pintype "bidirectional"))
      (node (ref "R82") (pin "1") (pinfunction "1_1") (pintype "passive"))
    )
    (net (code "90") (name "Net-(IC12-VS)") (class "Default")
      (node (ref "IC12") (pin "4") (pinfunction "VS_4") (pintype "bidirectional"))
      (node (ref "IC13") (pin "6") (pinfunction "S1_6") (pintype "bidirectional"))
    )
    (net (code "91") (name "Net-(IC13-D)") (class "Default")
      (node (ref "IC13") (pin "5") (pinfunction "D_5") (pintype "bidirectional"))
      (node (ref "R81") (pin "1") (pinfunction "1_1") (pintype "passive"))
    )
    (net (code "92") (name "Net-(IC14-AIN0{slash}REFP1)") (class "Default")
      (node (ref "C71") (pin "2") (pinfunction "2_2") (pintype "passive"))
      (node (ref "IC14") (pin "11") (pinfunction "AIN0/REFP1_11") (pintype "input"))
      (node (ref "R81") (pin "2") (pinfunction "2_2") (pintype "passive"))
    )
    (net (code "93") (name "Net-(IC14-AIN1)") (class "Default")
      (node (ref "C78") (pin "2") (pinfunction "2_2") (pintype "passive"))
      (node (ref "IC14") (pin "10") (pinfunction "AIN1_10") (pintype "input"))
      (node (ref "R83") (pin "2") (pinfunction "2_2") (pintype "passive"))
    )
    (net (code "94") (name "Net-(IC14-AIN2)") (class "Default")
      (node (ref "C77") (pin "2") (pinfunction "2_2") (pintype "passive"))
      (node (ref "IC14") (pin "7") (pinfunction "AIN2_7") (pintype "input"))
      (node (ref "R84") (pin "2") (pinfunction "2_2") (pintype "passive"))
    )
    (net (code "95") (name "Net-(IC14-AIN3{slash}REFN1)") (class "Default")
      (node (ref "C72") (pin "1") (pinfunction "1_1") (pintype "passive"))
      (node (ref "IC14") (pin "6") (pinfunction "AIN3/REFN1_6") (pintype "input"))
      (node (ref "R80") (pin "2") (pinfunction "2_2") (pintype "passive"))
    )
    (net (code "96") (name "Net-(IC14-AVDD)") (class "Default")
      (node (ref "C75") (pin "2") (pinfunction "2_2") (pintype "passive"))
      (node (ref "C76") (pin "2") (pinfunction "2_2") (pintype "passive"))
      (node (ref "IC14") (pin "12") (pinfunction "AVDD_12") (pintype "power_in"))
      (node (ref "R85") (pin "2") (pinfunction "2_2") (pintype "passive"))
    )
    (net (code "97") (name "Net-(IC15A-+IN)") (class "Default")
      (node (ref "IC15") (pin "7") (pinfunction "+IN_7") (pintype "input"))
      (node (ref "IC15") (pin "9") (pinfunction "+IN_9") (pintype "input"))
      (node (ref "R89") (pin "1") (pinfunction "1_1") (pintype "passive"))
      (node (ref "R94") (pin "2") (pinfunction "2_2") (pintype "passive"))
    )
    (net (code "98") (name "Net-(IC15A--IN)") (class "Default")
      (node (ref "IC15") (pin "5") (pinfunction "+IN_5") (pintype "input"))
      (node (ref "IC15") (pin "6") (pinfunction "-IN_6") (pintype "input"))
      (node (ref "R86") (pin "2") (pinfunction "2_2") (pintype "passive"))
    )
    (net (code "99") (name "Net-(IC15A-OUT)") (class "Default")
      (node (ref "IC15") (pin "1") (pinfunction "OUT_1") (pintype "open_collector"))
      (node (ref "IC15") (pin "2") (pinfunction "OUT_2") (pintype "open_collector"))
      (node (ref "R92") (pin "1") (pinfunction "1_1") (pintype "passive"))
    )
    (net (code "100") (name "Net-(IC15B--IN)") (class "Default")
      (node (ref "IC15") (pin "10") (pinfunction "-IN_10") (pintype "input"))
      (node (ref "IC15") (pin "4") (pinfunction "-IN_4") (pintype "input"))
      (node (ref "R102") (pin "2") (pinfunction "2_2") (pintype "passive"))
      (node (ref "R97") (pin "1") (pinfunction "1_1") (pintype "passive"))
    )
    (net (code "101") (name "Net-(IC15C--IN)") (class "Default")
      (node (ref "IC15") (pin "11") (pinfunction "+IN_11") (pintype "input"))
      (node (ref "IC15") (pin "8") (pinfunction "-IN_8") (pintype "input"))
      (node (ref "R106") (pin "2") (pinfunction "2_2") (pintype "passive"))
    )
    (net (code "102") (name "Net-(IC15C-OUT)") (class "Default")
      (node (ref "IC15") (pin "13") (pinfunction "OUT_13") (pintype "open_collector"))
      (node (ref "IC15") (pin "14") (pinfunction "OUT_14") (pintype "open_collector"))
      (node (ref "R104") (pin "1") (pinfunction "1_1") (pintype "passive"))
    )
    (net (code "103") (name "Net-(LED1-PadC)") (class "Default")
      (node (ref "LED1") (pin "C") (pinfunction "C_C") (pintype "passive"))
      (node (ref "R20") (pin "1") (pinfunction "1_1") (pintype "passive"))
    )
    (net (code "104") (name "Net-(Q3-D)") (class "Default")
      (node (ref "C23") (pin "1") (pinfunction "1_1") (pintype "passive"))
      (node (ref "Q2") (pin "C") (pinfunction "C_C") (pintype "passive"))
      (node (ref "Q3") (pin "3") (pinfunction "D_3") (pintype "passive"))
      (node (ref "R13") (pin "1") (pinfunction "1_1") (pintype "passive"))
    )
    (net (code "105") (name "Net-(Q4-PadS)") (class "Default")
      (node (ref "Q4") (pin "S") (pinfunction "S_S") (pintype "passive"))
      (node (ref "R30") (pin "1") (pinfunction "1_1") (pintype "passive"))
      (node (ref "R32") (pin "2") (pinfunction "2_2") (pintype "passive"))
      (node (ref "R33") (pin "2") (pinfunction "2_2") (pintype "passive"))
      (node (ref "R36") (pin "2") (pinfunction "2_2") (pintype "passive"))
      (node (ref "ZD4") (pin "A") (pinfunction "A_A") (pintype "passive"))
    )
    (net (code "106") (name "Net-(Q5-PadB)") (class "Default")
      (node (ref "Q5") (pin "B") (pinfunction "B_B") (pintype "passive"))
      (node (ref "R34") (pin "2") (pinfunction "2_2") (pintype "passive"))
    )
    (net (code "107") (name "Net-(Q6-PadB)") (class "Default")
      (node (ref "Q6") (pin "B") (pinfunction "B_B") (pintype "passive"))
      (node (ref "R33") (pin "1") (pinfunction "1_1") (pintype "passive"))
    )
    (net (code "108") (name "Net-(Q7-B)") (class "Default")
      (node (ref "D14") (pin "A") (pinfunction "A_A") (pintype "passive"))
      (node (ref "Q7") (pin "1") (pinfunction "B_1") (pintype "passive"))
      (node (ref "R40") (pin "2") (pinfunction "2_2") (pintype "passive"))
      (node (ref "R43") (pin "1") (pinfunction "1_1") (pintype "passive"))
    )
    (net (code "109") (name "Net-(Q7-E)") (class "Default")
      (node (ref "D11") (pin "A") (pinfunction "A_A") (pintype "passive"))
      (node (ref "Q7") (pin "3") (pinfunction "E_3") (pintype "passive"))
    )
    (net (code "110") (name "Net-(Q8-G)") (class "Default")
      (node (ref "D13") (pin "A") (pinfunction "A_A") (pintype "passive"))
      (node (ref "Q5") (pin "C") (pinfunction "C_C") (pintype "passive"))
      (node (ref "Q8") (pin "1") (pinfunction "G_1") (pintype "passive"))
      (node (ref "R35") (pin "2") (pinfunction "2_2") (pintype "passive"))
    )
    (net (code "111") (name "Net-(Q8-S)") (class "Default")
      (node (ref "Q8") (pin "3") (pinfunction "S_3") (pintype "passive"))
      (node (ref "R31") (pin "1") (pinfunction "1_1") (pintype "passive"))
      (node (ref "R34") (pin "1") (pinfunction "1_1") (pintype "passive"))
      (node (ref "R35") (pin "1") (pinfunction "1_1") (pintype "passive"))
    )
    (net (code "112") (name "Net-(Q9-E)") (class "Default")
      (node (ref "Q9") (pin "3") (pinfunction "E_3") (pintype "passive"))
      (node (ref "R42") (pin "1") (pinfunction "1_1") (pintype "passive"))
    )
    (net (code "113") (name "Net-(Q10-PadB)") (class "Default")
      (node (ref "Q10") (pin "B") (pinfunction "B_B") (pintype "passive"))
      (node (ref "Q10") (pin "C") (pinfunction "C_C") (pintype "passive"))
      (node (ref "Q11") (pin "B") (pinfunction "B_B") (pintype "passive"))
      (node (ref "Q13") (pin "C") (pinfunction "C_C") (pintype "passive"))
    )
    (net (code "114") (name "Net-(Q10-PadE)") (class "Default")
      (node (ref "Q10") (pin "E") (pinfunction "E_E") (pintype "passive"))
      (node (ref "R38") (pin "1") (pinfunction "1_1") (pintype "passive"))
    )
    (net (code "115") (name "Net-(Q11-PadE)") (class "Default")
      (node (ref "Q11") (pin "E") (pinfunction "E_E") (pintype "passive"))
      (node (ref "R39") (pin "1") (pinfunction "1_1") (pintype "passive"))
    )
    (net (code "116") (name "Net-(Q12-PadB)") (class "Default")
      (node (ref "Q12") (pin "B") (pinfunction "B_B") (pintype "passive"))
      (node (ref "R36") (pin "1") (pinfunction "1_1") (pintype "passive"))
      (node (ref "R46") (pin "2") (pinfunction "2_2") (pintype "passive"))
      (node (ref "R47") (pin "2") (pinfunction "2_2") (pintype "passive"))
    )
    (net (code "117") (name "Net-(Q12-PadE)") (class "Default")
      (node (ref "Q12") (pin "E") (pinfunction "E_E") (pintype "passive"))
      (node (ref "R53") (pin "2") (pinfunction "2_2") (pintype "passive"))
    )
    (net (code "118") (name "Net-(Q13-PadE)") (class "Default")
      (node (ref "Q13") (pin "E") (pinfunction "E_E") (pintype "passive"))
      (node (ref "R56") (pin "2") (pinfunction "2_2") (pintype "passive"))
    )
    (net (code "119") (name "Net-(Q14-D)") (class "Default")
      (node (ref "Q14") (pin "3") (pinfunction "D_3") (pintype "passive"))
      (node (ref "R78") (pin "2") (pinfunction "2_2") (pintype "passive"))
    )
    (net (code "120") (name "Net-(Q18-PadB)") (class "Default")
      (node (ref "Q18") (pin "B") (pinfunction "B_B") (pintype "passive"))
      (node (ref "R103") (pin "2") (pinfunction "2_2") (pintype "passive"))
      (node (ref "R99") (pin "1") (pinfunction "1_1") (pintype "passive"))
    )
    (net (code "121") (name "Net-(Q19-PadC)") (class "Default")
      (node (ref "Q19") (pin "C") (pinfunction "C_C") (pintype "passive"))
      (node (ref "R95") (pin "1") (pinfunction "1_1") (pintype "passive"))
    )
    (net (code "122") (name "Net-(R4-Pad2)") (class "Default")
      (node (ref "R4") (pin "2") (pinfunction "2_2") (pintype "passive"))
      (node (ref "SW") (pin "P$1") (pinfunction "P$1_P$1") (pintype "bidirectional"))
    )
    (net (code "123") (name "Net-(R22-Pad1)") (class "Default")
      (node (ref "R22") (pin "1") (pinfunction "1_1") (pintype "passive"))
      (node (ref "R23") (pin "2") (pinfunction "2_2") (pintype "passive"))
    )
    (net (code "124") (name "Net-(R26-Pad2)") (class "Default")
      (node (ref "R26") (pin "2") (pinfunction "2_2") (pintype "passive"))
      (node (ref "R28") (pin "2") (pinfunction "2_2") (pintype "passive"))
    )
    (net (code "125") (name "Net-(R63-Pad2)") (class "Default")
      (node (ref "R63") (pin "2") (pinfunction "2_2") (pintype "passive"))
      (node (ref "R64") (pin "1") (pinfunction "1_1") (pintype "passive"))
    )
    (net (code "126") (name "Net-(R66-Pad1)") (class "Default")
      (node (ref "R66") (pin "1") (pinfunction "1_1") (pintype "passive"))
      (node (ref "R67") (pin "2") (pinfunction "2_2") (pintype "passive"))
    )
    (net (code "127") (name "Net-(R70-Pad1)") (class "Default")
      (node (ref "R70") (pin "1") (pinfunction "1_1") (pintype "passive"))
      (node (ref "R71") (pin "2") (pinfunction "2_2") (pintype "passive"))
    )
    (net (code "128") (name "Net-(R72-Pad1)") (class "Default")
      (node (ref "R72") (pin "1") (pinfunction "1_1") (pintype "passive"))
      (node (ref "R73") (pin "2") (pinfunction "2_2") (pintype "passive"))
    )
    (net (code "129") (name "Net-(R74-Pad2)") (class "Default")
      (node (ref "R74") (pin "2") (pinfunction "2_2") (pintype "passive"))
      (node (ref "R75") (pin "1") (pinfunction "1_1") (pintype "passive"))
    )
    (net (code "130") (name "Net-(R95-Pad2)") (class "Default")
      (node (ref "R95") (pin "2") (pinfunction "2_2") (pintype "passive"))
      (node (ref "R96") (pin "1") (pinfunction "1_1") (pintype "passive"))
    )
    (net (code "131") (name "Net-(X3H-1)") (class "Default")
      (node (ref "R21") (pin "2") (pinfunction "2_2") (pintype "passive"))
      (node (ref "X3") (pin "16") (pinfunction "1_16") (pintype "passive"))
    )
    (net (code "132") (name "OUT+") (class "Default")
      (node (ref "C48") (pin "2") (pinfunction "2_2") (pintype "passive"))
      (node (ref "C51") (pin "1") (pinfunction "1_1") (pintype "passive"))
      (node (ref "C64") (pin "1") (pinfunction "1_1") (pintype "passive"))
      (node (ref "C80") (pin "1") (pinfunction "1_1") (pintype "passive"))
      (node (ref "Q17") (pin "E") (pinfunction "E_E") (pintype "passive"))
      (node (ref "Q5") (pin "E") (pinfunction "E_E") (pintype "passive"))
      (node (ref "Q6") (pin "E") (pinfunction "E_E") (pintype "passive"))
      (node (ref "R14") (pin "2") (pinfunction "2_2") (pintype "passive"))
      (node (ref "R30") (pin "2") (pinfunction "2_2") (pintype "passive"))
      (node (ref "R31") (pin "2") (pinfunction "2_2") (pintype "passive"))
      (node (ref "R37") (pin "1") (pinfunction "1_1") (pintype "passive"))
      (node (ref "R87") (pin "2") (pinfunction "2_2") (pintype "passive"))
      (node (ref "TP1") (pin "TIP") (pinfunction "TIP_TIP") (pintype "bidirectional"))
      (node (ref "X3") (pin "23") (pinfunction "1_23") (pintype "passive"))
      (node (ref "X3") (pin "24") (pinfunction "1_24") (pintype "passive"))
      (node (ref "X3") (pin "25") (pinfunction "1_25") (pintype "passive"))
      (node (ref "X3") (pin "26") (pinfunction "1_26") (pintype "passive"))
      (node (ref "ZD3") (pin "C") (pinfunction "1_C") (pintype "passive"))
    )
    (net (code "133") (name "OUT-") (class "Default")
      (node (ref "C47") (pin "1") (pinfunction "1_1") (pintype "passive"))
      (node (ref "C49") (pin "2") (pinfunction "2_2") (pintype "passive"))
      (node (ref "C84") (pin "2") (pinfunction "2_2") (pintype "passive"))
      (node (ref "Q19") (pin "E") (pinfunction "E_E") (pintype "passive"))
      (node (ref "R105") (pin "1") (pinfunction "1_1") (pintype "passive"))
      (node (ref "R62") (pin "2") (pinfunction "2_2") (pintype "passive"))
      (node (ref "R67") (pin "1") (pinfunction "1_1") (pintype "passive"))
      (node (ref "R69") (pin "1") (pinfunction "1_1") (pintype "passive"))
      (node (ref "X3") (pin "17") (pinfunction "1_17") (pintype "passive"))
      (node (ref "X3") (pin "18") (pinfunction "1_18") (pintype "passive"))
      (node (ref "X3") (pin "19") (pinfunction "1_19") (pintype "passive"))
      (node (ref "X3") (pin "20") (pinfunction "1_20") (pintype "passive"))
      (node (ref "ZD3") (pin "A") (pinfunction "2_A") (pintype "passive"))
    )
    (net (code "134") (name "POST_OE") (class "Default")
      (node (ref "Q15") (pin "3") (pinfunction "D_3") (pintype "passive"))
      (node (ref "R56") (pin "1") (pinfunction "1_1") (pintype "passive"))
    )
    (net (code "135") (name "POUT-") (class "Default")
      (node (ref "C13") (pin "2") (pinfunction "2_2") (pintype "passive"))
      (node (ref "C14") (pin "2") (pinfunction "2_2") (pintype "passive"))
      (node (ref "C15") (pin "2") (pinfunction "2_2") (pintype "passive"))
      (node (ref "C16") (pin "2") (pinfunction "2_2") (pintype "passive"))
      (node (ref "C19") (pin "1") (pinfunction "1_1") (pintype "passive"))
      (node (ref "R69") (pin "2") (pinfunction "2_2") (pintype "passive"))
      (node (ref "R71") (pin "1") (pinfunction "1_1") (pintype "passive"))
      (node (ref "SH1") (pin "P$1") (pinfunction "GND_A_P$1") (pintype "bidirectional"))
    )
    (net (code "136") (name "PREG_OUT") (class "Default")
      (node (ref "C14") (pin "1") (pinfunction "1_1") (pintype "passive"))
      (node (ref "C15") (pin "1") (pinfunction "1_1") (pintype "passive"))
      (node (ref "C16") (pin "1") (pinfunction "1_1") (pintype "passive"))
      (node (ref "L4") (pin "2") (pinfunction "2_2") (pintype "passive"))
      (node (ref "Q4") (pin "D") (pinfunction "D_D") (pintype "passive"))
      (node (ref "R6") (pin "2") (pinfunction "2_2") (pintype "passive"))
    )
    (net (code "137") (name "PRE_OE") (class "Default")
      (node (ref "IC9") (pin "17") (pinfunction "GP7_17") (pintype "bidirectional"))
      (node (ref "Q15") (pin "1") (pinfunction "G_1") (pintype "passive"))
      (node (ref "R3") (pin "2") (pinfunction "2_2") (pintype "passive"))
      (node (ref "R79") (pin "2") (pinfunction "2_2") (pintype "passive"))
    )
    (net (code "138") (name "PS_MISO") (class "Default")
      (node (ref "IC14") (pin "15") (pinfunction "DOUT/~{DRDY}_15") (pintype "output"))
      (node (ref "IC9") (pin "3") (pinfunction "SO_3") (pintype "output"))
      (node (ref "X3") (pin "9") (pinfunction "1_9") (pintype "passive"))
    )
    (net (code "139") (name "PS_MOSI") (class "Default")
      (node (ref "IC11") (pin "7") (pinfunction "DIN_7") (pintype "input"))
      (node (ref "IC14") (pin "16") (pinfunction "DIN_16") (pintype "input"))
      (node (ref "IC9") (pin "2") (pinfunction "SI_2") (pintype "input"))
      (node (ref "X3") (pin "1") (pinfunction "1_1") (pintype "passive"))
    )
    (net (code "140") (name "PS_SCLK") (class "Default")
      (node (ref "IC11") (pin "6") (pinfunction "SCLK_6") (pintype "input"))
      (node (ref "IC14") (pin "1") (pinfunction "SCLK_1") (pintype "input"))
      (node (ref "IC9") (pin "1") (pinfunction "SCK_1") (pintype "input"))
      (node (ref "X3") (pin "7") (pinfunction "1_7") (pintype "passive"))
    )
    (net (code "141") (name "PWRGOOD") (class "Default")
      (node (ref "IC5") (pin "5") (pinfunction "~{ERROR}_5") (pintype "input"))
      (node (ref "IC9") (pin "16") (pinfunction "GP6_16") (pintype "bidirectional"))
      (node (ref "R29") (pin "2") (pinfunction "2_2") (pintype "passive"))
    )
    (net (code "142") (name "SENSE+") (class "Default")
      (node (ref "C46") (pin "1") (pinfunction "1_1") (pintype "passive"))
      (node (ref "R37") (pin "2") (pinfunction "2_2") (pintype "passive"))
      (node (ref "R50") (pin "2") (pinfunction "2_2") (pintype "passive"))
      (node (ref "R93") (pin "1") (pinfunction "1_1") (pintype "passive"))
      (node (ref "X3") (pin "22") (pinfunction "1_22") (pintype "passive"))
    )
    (net (code "143") (name "SENSE-") (class "Default")
      (node (ref "C52") (pin "1") (pinfunction "1_1") (pintype "passive"))
      (node (ref "R100") (pin "2") (pinfunction "2_2") (pintype "passive"))
      (node (ref "R60") (pin "2") (pinfunction "2_2") (pintype "passive"))
      (node (ref "R62") (pin "1") (pinfunction "1_1") (pintype "passive"))
      (node (ref "X3") (pin "21") (pinfunction "1_21") (pintype "passive"))
    )
    (net (code "144") (name "SENSE_ERR") (class "Default")
      (node (ref "IC9") (pin "10") (pinfunction "GP0_10") (pintype "bidirectional"))
      (node (ref "Q18") (pin "C") (pinfunction "C_C") (pintype "passive"))
      (node (ref "R98") (pin "1") (pinfunction "1_1") (pintype "passive"))
    )
    (net (code "145") (name "SENSE_PROT") (class "Default")
      (node (ref "Q11") (pin "C") (pinfunction "C_C") (pintype "passive"))
      (node (ref "Q12") (pin "C") (pinfunction "C_C") (pintype "passive"))
      (node (ref "Q16") (pin "C") (pinfunction "C_C") (pintype "passive"))
      (node (ref "R43") (pin "2") (pinfunction "2_2") (pintype "passive"))
      (node (ref "R51") (pin "2") (pinfunction "2_2") (pintype "passive"))
    )
    (net (code "146") (name "SGND") (class "Default")
      (node (ref "C11") (pin "1") (pinfunction "1_1") (pintype "passive"))
      (node (ref "C21") (pin "2") (pinfunction "2_2") (pintype "passive"))
      (node (ref "C22") (pin "2") (pinfunction "2_2") (pintype "passive"))
      (node (ref "IC1") (pin "3") (pinfunction "SGND_3") (pintype "passive"))
      (node (ref "JP1") (pin "1") (pinfunction "1_1") (pintype "passive"))
      (node (ref "R15") (pin "2") (pinfunction "2_2") (pintype "passive"))
      (node (ref "R7") (pin "2") (pinfunction "2_2") (pintype "passive"))
      (node (ref "SH2") (pin "P$1") (pinfunction "GND_A_P$1") (pintype "bidirectional"))
    )
    (net (code "147") (name "SYNC") (class "Default")
      (node (ref "IC4") (pin "4") (pinfunction "SYNC_4") (pintype "input"))
      (node (ref "JP1") (pin "3") (pinfunction "3_3") (pintype "passive"))
      (node (ref "R21") (pin "1") (pinfunction "1_1") (pintype "passive"))
    )
    (net (code "148") (name "TEMP_NTC") (class "Default")
      (node (ref "NTC1") (pin "1") (pinfunction "P$1_1") (pintype "bidirectional"))
      (node (ref "NTC1") (pin "1.1") (pinfunction "P$1_1.1") (pintype "bidirectional"))
      (node (ref "X3") (pin "13") (pinfunction "1_13") (pintype "passive"))
    )
    (net (code "149") (name "U_MON") (class "Default")
      (node (ref "IC6") (pin "7") (pinfunction "OUT_7") (pintype "output"))
      (node (ref "R54") (pin "1") (pinfunction "1_1") (pintype "passive"))
      (node (ref "R55") (pin "1") (pinfunction "1_1") (pintype "passive"))
      (node (ref "R83") (pin "1") (pinfunction "1_1") (pintype "passive"))
    )
    (net (code "150") (name "U_SERVO") (class "Default")
      (node (ref "D15") (pin "C") (pinfunction "C_C") (pintype "passive"))
      (node (ref "D16") (pin "A") (pinfunction "A_A") (pintype "passive"))
      (node (ref "IC6") (pin "1") (pinfunction "OUT_1") (pintype "output"))
      (node (ref "R57") (pin "2") (pinfunction "2_2") (pintype "passive"))
      (node (ref "R86") (pin "1") (pinfunction "1_1") (pintype "passive"))
    )
    (net (code "151") (name "U_SET_OUT") (class "Default")
      (node (ref "IC11") (pin "4") (pinfunction "VOUTA_4") (pintype "output"))
      (node (ref "IC13") (pin "4") (pinfunction "S2_4") (pintype "bidirectional"))
      (node (ref "R52") (pin "1") (pinfunction "1_1") (pintype "passive"))
    )
    (net (code "152") (name "V+") (class "Default")
      (node (ref "C53") (pin "2") (pinfunction "2_2") (pintype "passive"))
      (node (ref "C54") (pin "1") (pinfunction "1_1") (pintype "passive"))
      (node (ref "C55") (pin "2") (pinfunction "2_2") (pintype "passive"))
      (node (ref "C56") (pin "2") (pinfunction "2_2") (pintype "passive"))
      (node (ref "C57") (pin "2") (pinfunction "2_2") (pintype "passive"))
      (node (ref "C66") (pin "1") (pinfunction "1_1") (pintype "passive"))
      (node (ref "C69") (pin "2") (pinfunction "2_2") (pintype "passive"))
      (node (ref "C82") (pin "2") (pinfunction "2_2") (pintype "passive"))
      (node (ref "FB2") (pin "P$2") (pinfunction "2_P$2") (pintype "passive"))
      (node (ref "IC10") (pin "2") (pinfunction "VIN_2") (pintype "passive"))
      (node (ref "IC11") (pin "1") (pinfunction "VDD_1") (pintype "power_in"))
      (node (ref "IC12") (pin "6") (pinfunction "VDD_6") (pintype "bidirectional"))
      (node (ref "IC13") (pin "2") (pinfunction "VDD_2") (pintype "power_in"))
      (node (ref "IC15") (pin "3") (pinfunction "V+_3") (pintype "power_in"))
      (node (ref "IC6") (pin "8") (pinfunction "V+_8") (pintype "power_in"))
      (node (ref "IC7") (pin "8") (pinfunction "V+_8") (pintype "power_in"))
      (node (ref "IC8") (pin "7") (pinfunction "V+_7") (pintype "power_in"))
      (node (ref "R85") (pin "1") (pinfunction "1_1") (pintype "passive"))
      (node (ref "R89") (pin "2") (pinfunction "2_2") (pintype "passive"))
    )
    (net (code "153") (name "V-") (class "Default")
      (node (ref "C58") (pin "2") (pinfunction "2_2") (pintype "passive"))
      (node (ref "C59") (pin "2") (pinfunction "2_2") (pintype "passive"))
      (node (ref "C60") (pin "1") (pinfunction "1_1") (pintype "passive"))
      (node (ref "C61") (pin "2") (pinfunction "2_2") (pintype "passive"))
      (node (ref "C62") (pin "2") (pinfunction "2_2") (pintype "passive"))
      (node (ref "C83") (pin "2") (pinfunction "2_2") (pintype "passive"))
      (node (ref "FB1") (pin "P$2") (pinfunction "2_P$2") (pintype "passive"))
      (node (ref "IC12") (pin "3") (pinfunction "VSS_3") (pintype "bidirectional"))
      (node (ref "IC15") (pin "12") (pinfunction "GND_12") (pintype "power_in"))
      (node (ref "IC6") (pin "4") (pinfunction "V-_4") (pintype "power_in"))
      (node (ref "IC7") (pin "4") (pinfunction "V-_4") (pintype "power_in"))
      (node (ref "IC8") (pin "4") (pinfunction "V-_4") (pintype "power_in"))
      (node (ref "R102") (pin "1") (pinfunction "1_1") (pintype "passive"))
    )
    (net (code "154") (name "unconnected-(IC1-PGOOD-Pad7)") (class "Default")
      (node (ref "IC1") (pin "7") (pinfunction "PGOOD_7") (pintype "output"))
    )
    (net (code "155") (name "unconnected-(IC5-SD-Pad3)") (class "Default")
      (node (ref "IC5") (pin "3") (pinfunction "SD_3") (pintype "input"))
    )
    (net (code "156") (name "unconnected-(IC5-SENSE-Pad2)") (class "Default")
      (node (ref "IC5") (pin "2") (pinfunction "SENSE_2") (pintype "input"))
    )
    (net (code "157") (name "unconnected-(IC5-VTAP-Pad6)") (class "Default")
      (node (ref "IC5") (pin "6") (pinfunction "VTAP_6") (pintype "input"))
    )
    (net (code "158") (name "unconnected-(IC10-TEMP-Pad3)") (class "Default")
      (node (ref "IC10") (pin "3") (pinfunction "TEMP_3") (pintype "input"))
    )
    (net (code "159") (name "~{DP_DRIVE}") (class "Default")
      (node (ref "Q9") (pin "1") (pinfunction "B_1") (pintype "passive"))
      (node (ref "R41") (pin "1") (pinfunction "1_1") (pintype "passive"))
      (node (ref "R78") (pin "1") (pinfunction "1_1") (pintype "passive"))
    )
    (net (code "160") (name "~{INT}") (class "Default")
      (node (ref "JP2") (pin "2") (pinfunction "2_2") (pintype "passive"))
      (node (ref "X3") (pin "8") (pinfunction "1_8") (pintype "passive"))
    )
    (net (code "161") (name "~{PS_DRDY}") (class "Default")
      (node (ref "IC14") (pin "14") (pinfunction "~{DRDY}_14") (pintype "output"))
      (node (ref "JP2") (pin "3") (pinfunction "3_3") (pintype "passive"))
    )
    (net (code "162") (name "~{PS_RESET}") (class "Default")
      (node (ref "IC9") (pin "6") (pinfunction "~{RESET}_6") (pintype "input"))
      (node (ref "X3") (pin "5") (pinfunction "1_5") (pintype "passive"))
    )
    (net (code "163") (name "~{SET_100%}") (class "Default")
      (node (ref "IC9") (pin "13") (pinfunction "GP3_13") (pintype "bidirectional"))
      (node (ref "Q3") (pin "1") (pinfunction "G_1") (pintype "passive"))
    )
    (net (code "164") (name "~{SET_DP}") (class "Default")
      (node (ref "IC9") (pin "11") (pinfunction "GP1_11") (pintype "bidirectional"))
      (node (ref "Q14") (pin "1") (pinfunction "G_1") (pintype "passive"))
      (node (ref "R77") (pin "2") (pinfunction "2_2") (pintype "passive"))
    )
  )
)
